# room_sensors.net
KiCad netlist of a schematic drawn in EAGLE
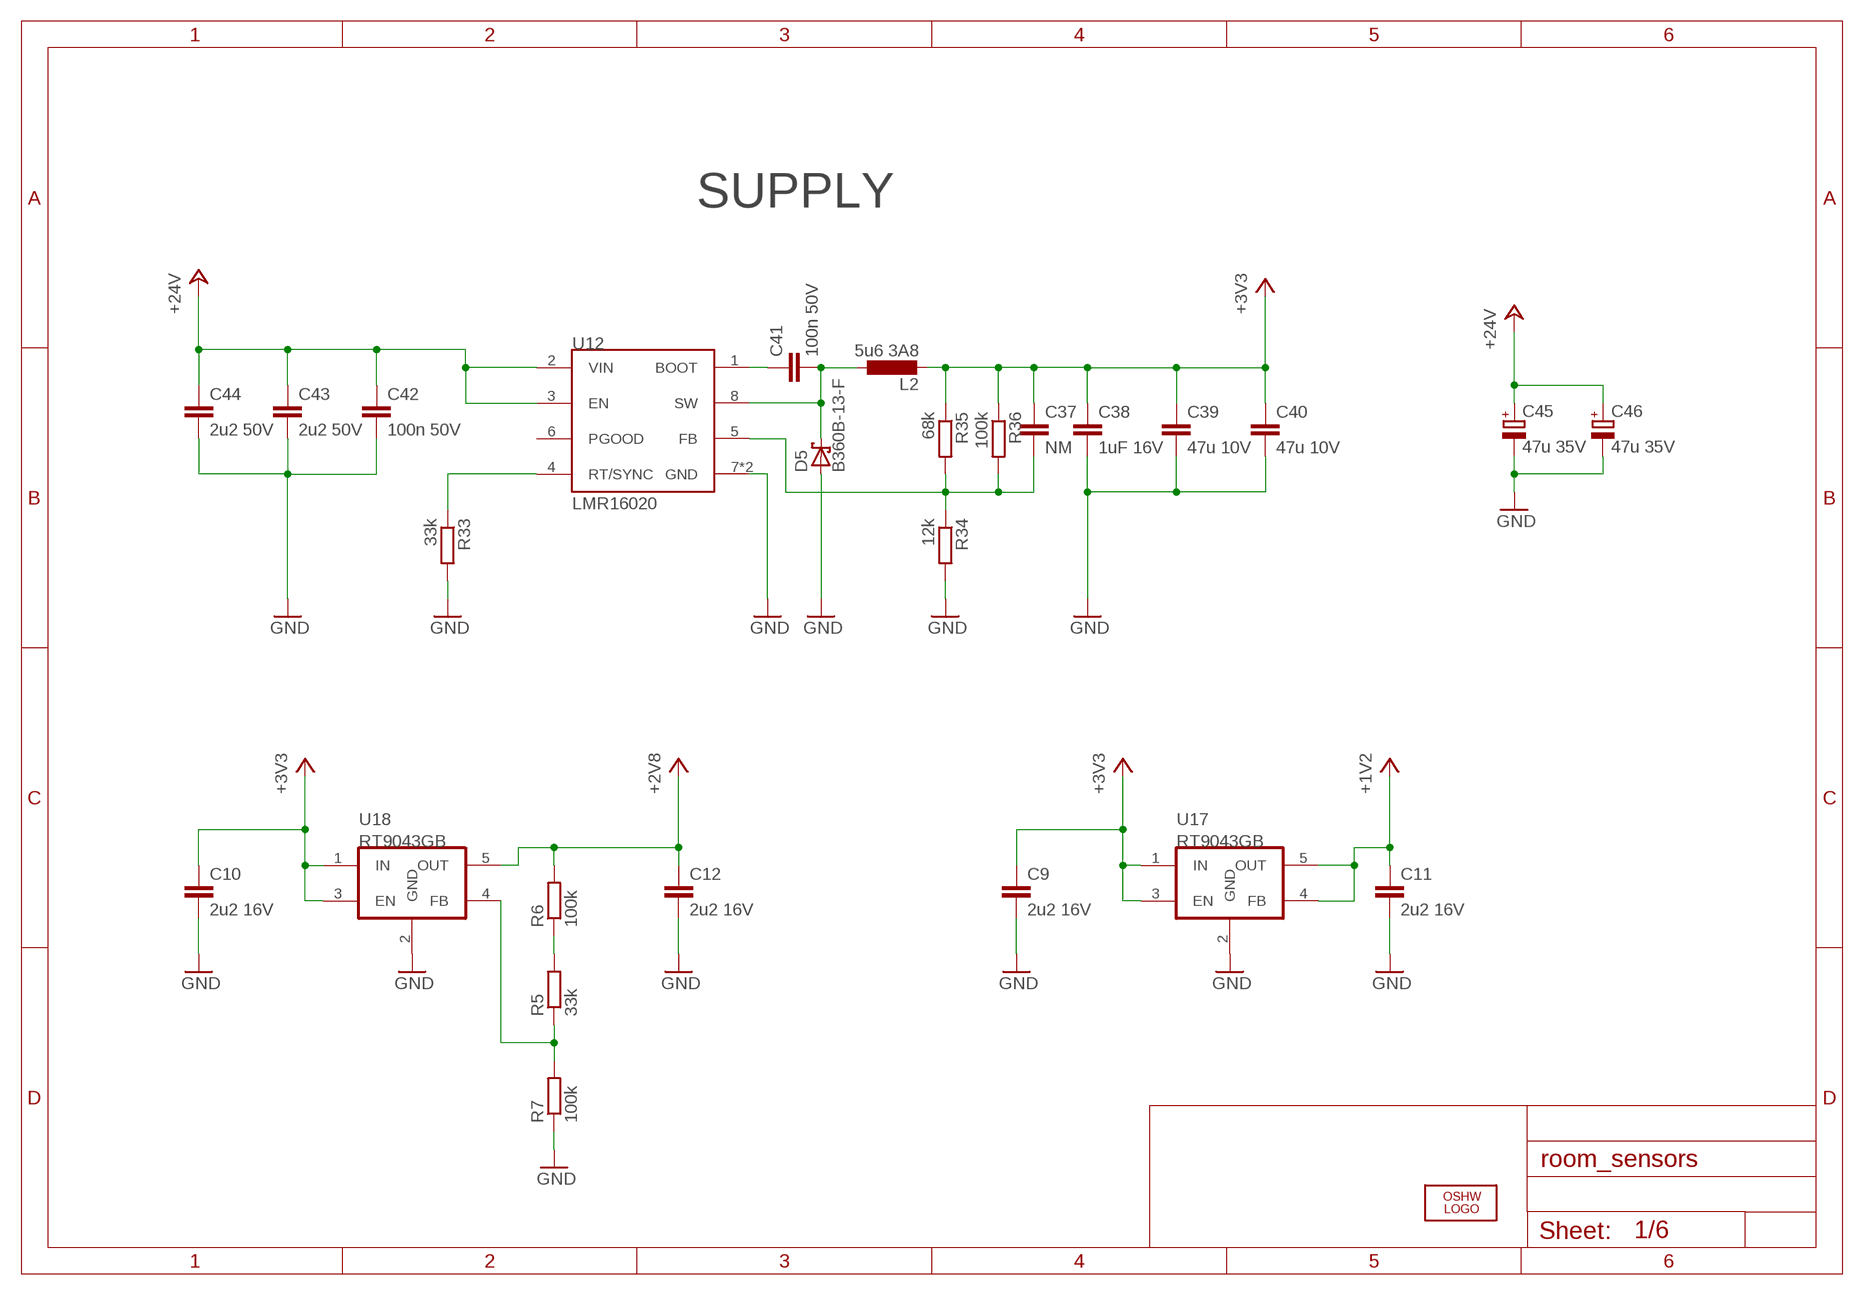
[diagram p0: schematic, sheet 1]
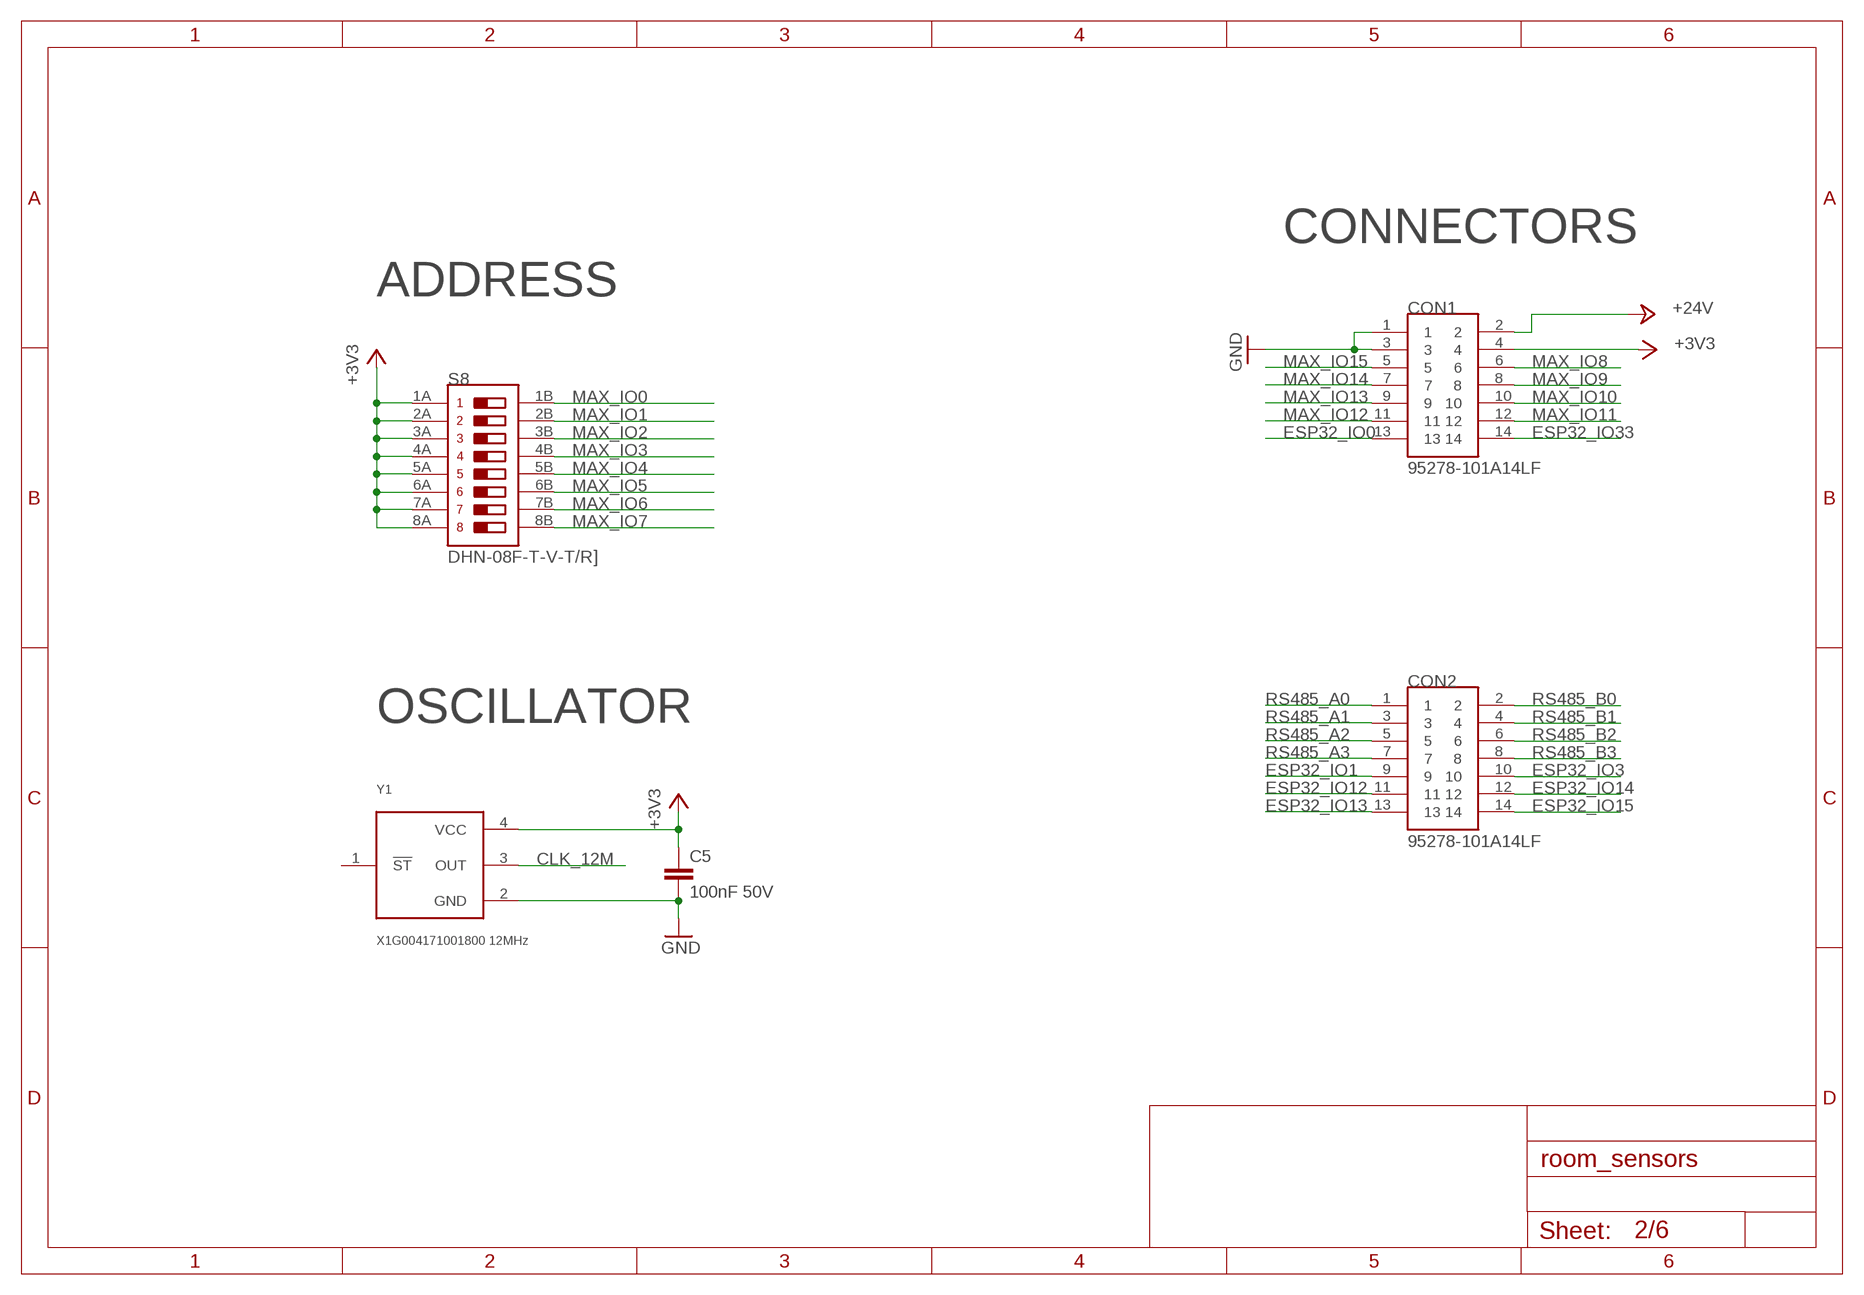
[diagram p1: schematic, sheet 2]
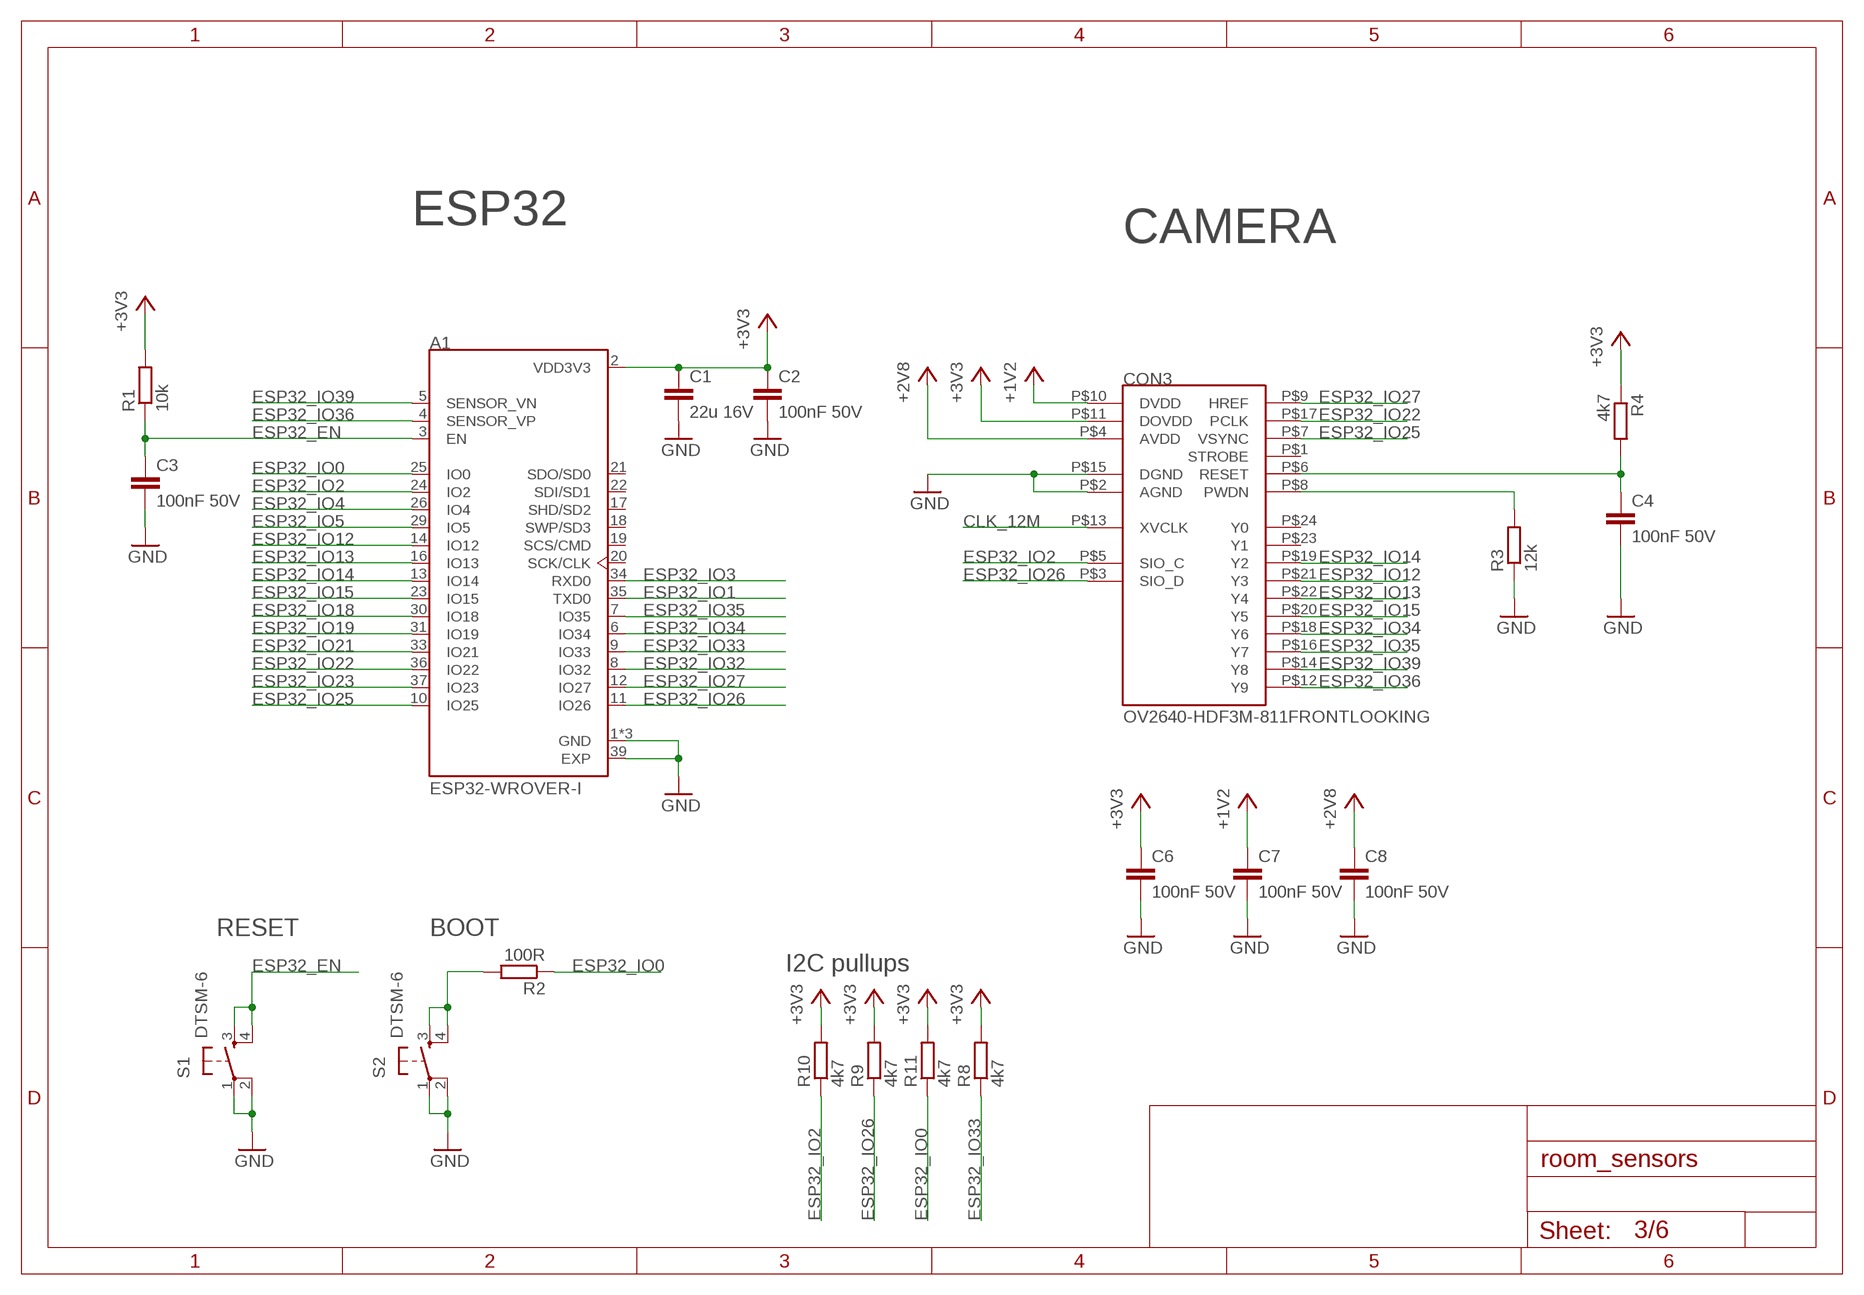
[diagram p2: schematic, sheet 3]
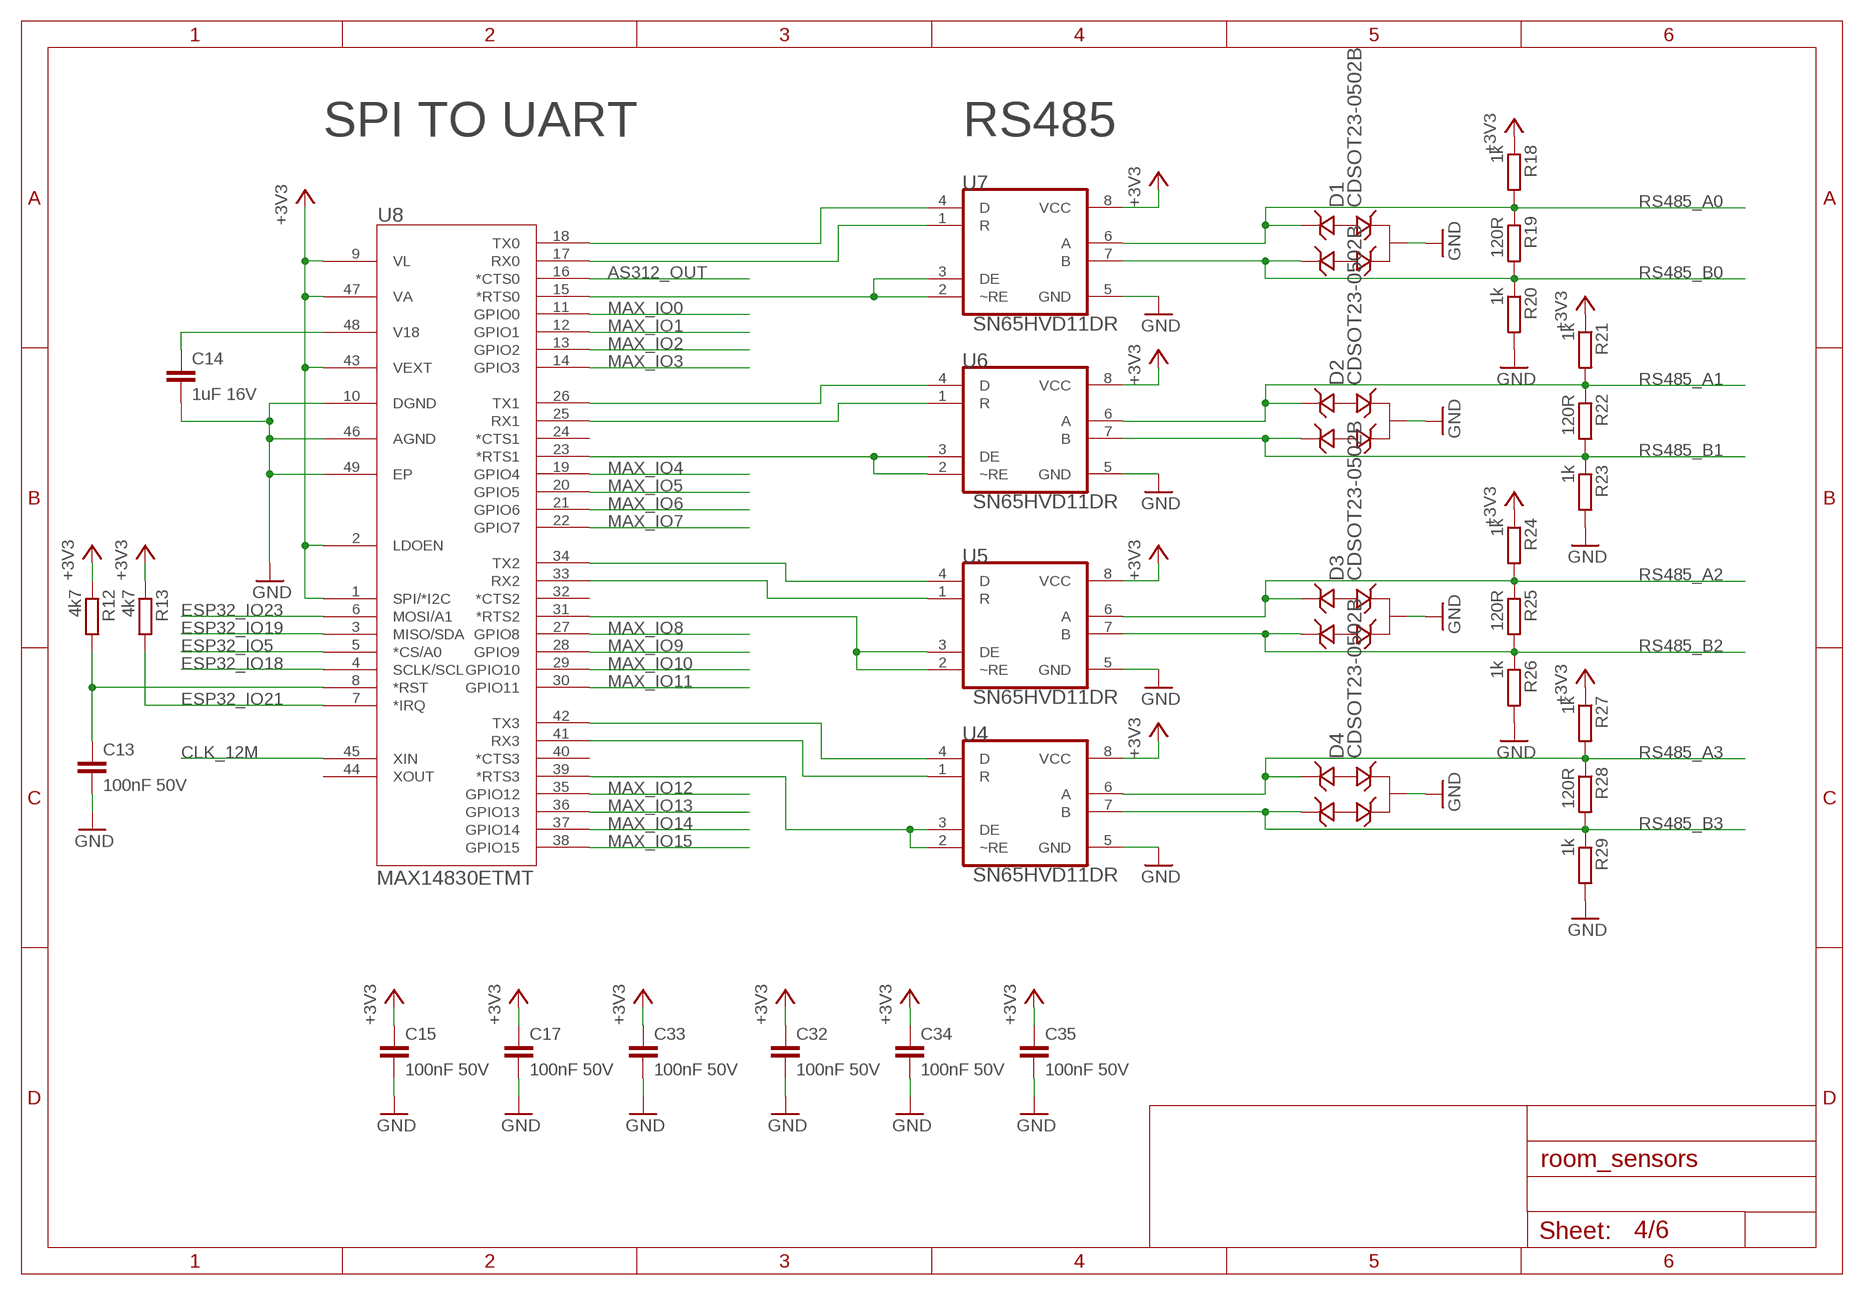
[diagram p3: schematic, sheet 4]
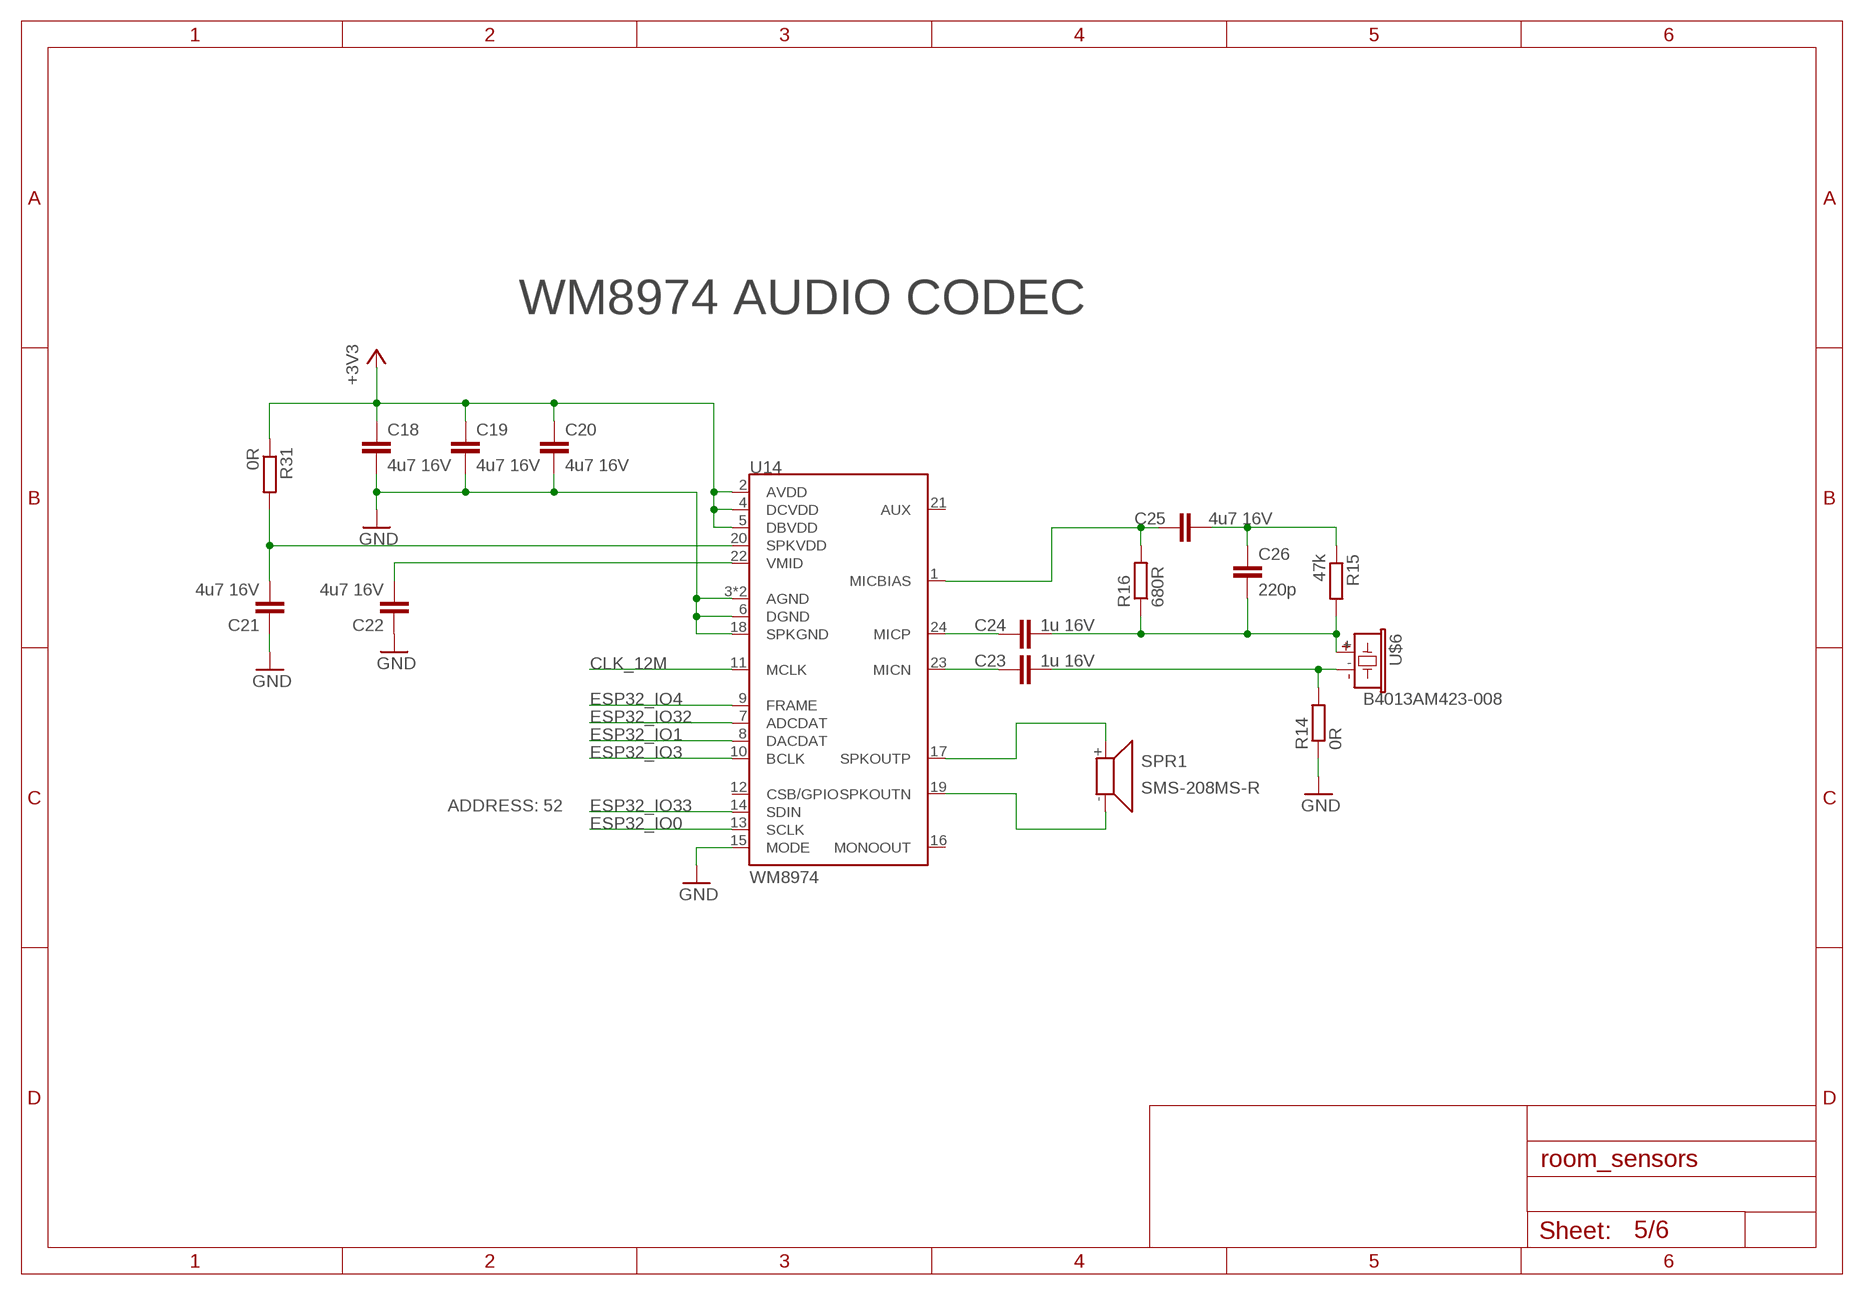
[diagram p4: schematic, sheet 5]
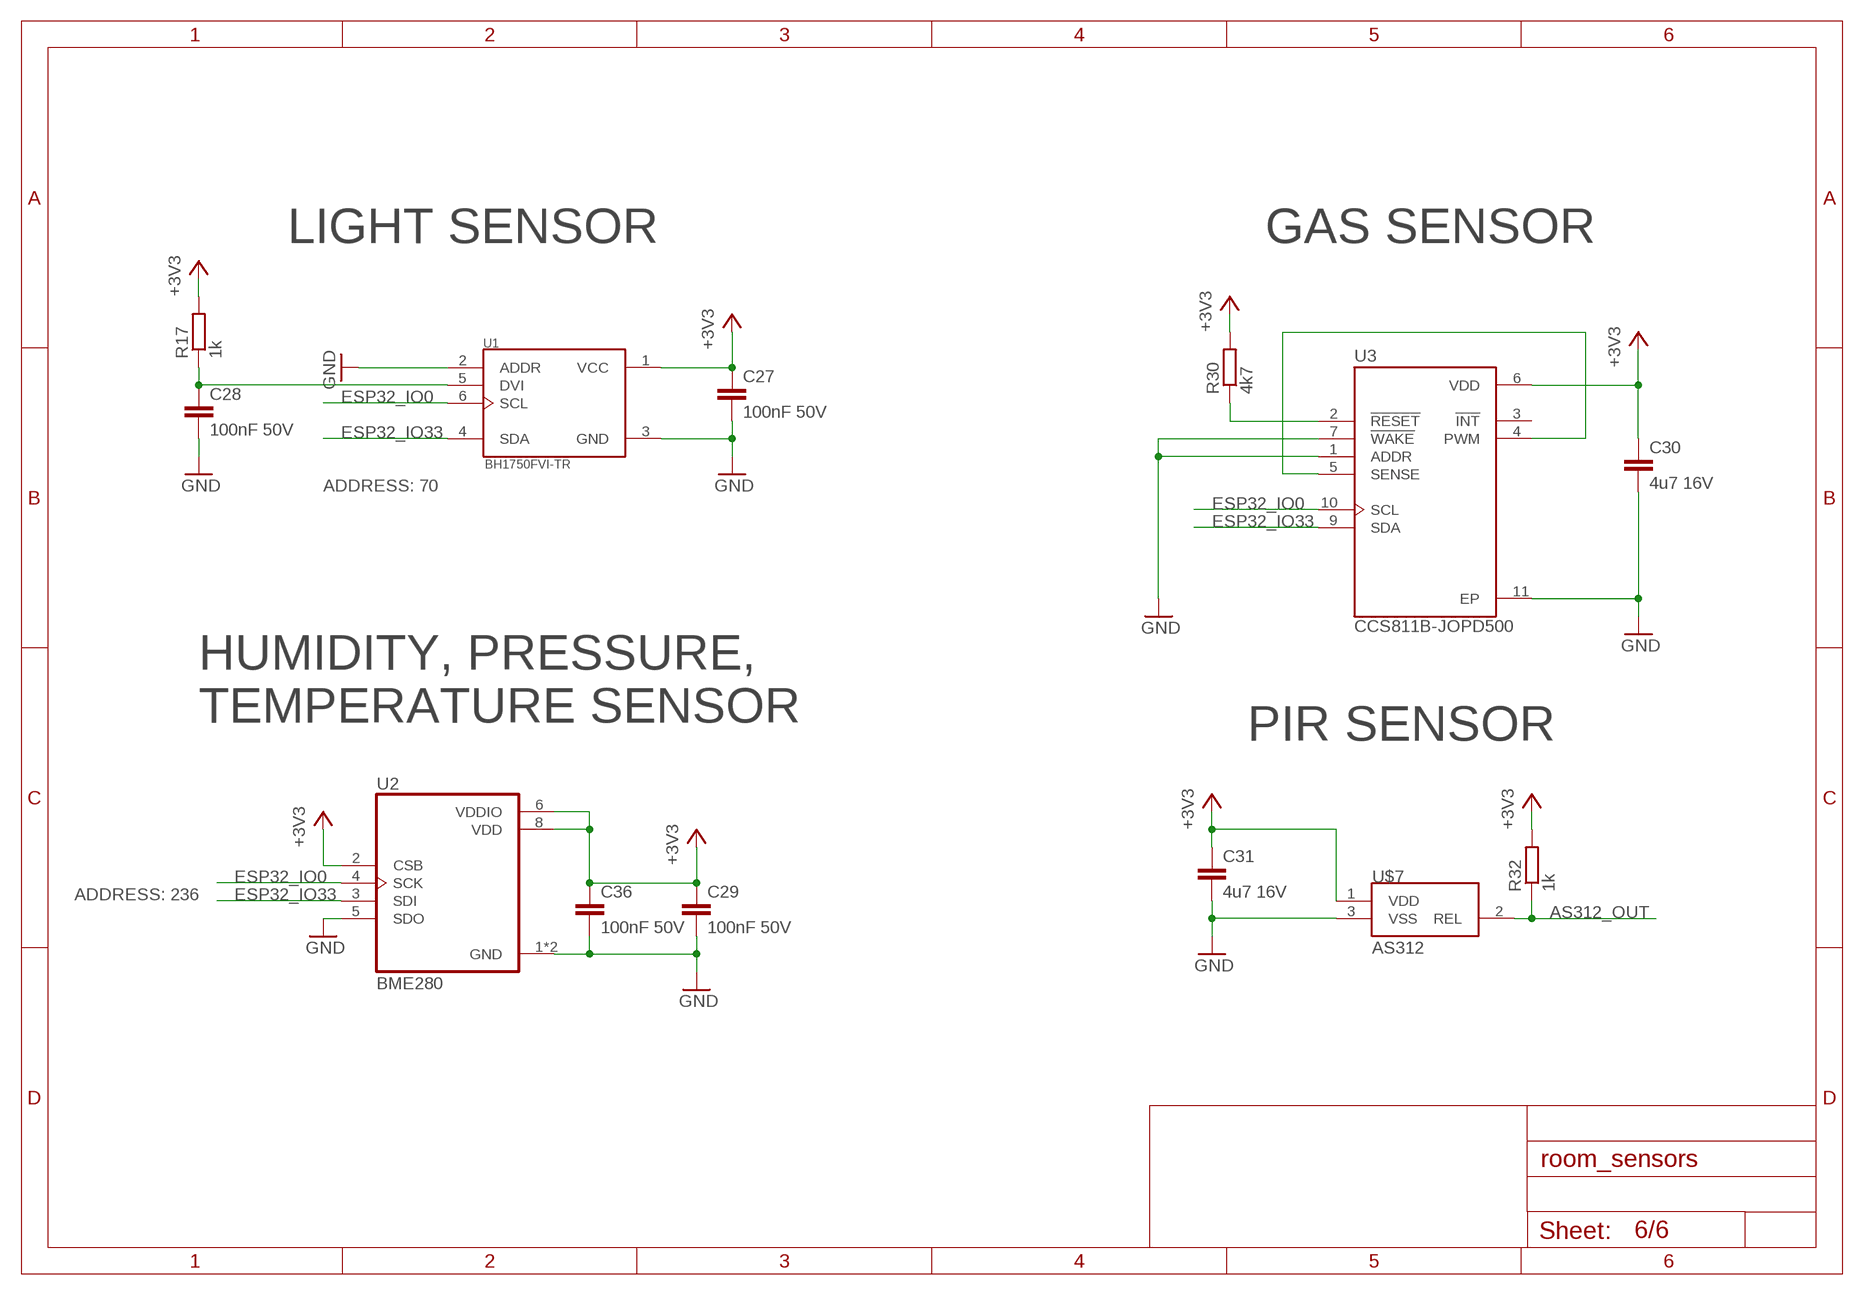
[diagram p5: schematic, sheet 6]

(export (version "E")
  (design (tool "Eeschema 10.0.6"))
  (components
    (comp (ref "C9")
      (value "2u2 16V")
      (footprint "eagle-import:C1206")
      (libsource (lib "eagle-import") (part "C-EUC1206"))
    )
    (comp (ref "C10")
      (value "2u2 16V")
      (footprint "eagle-import:C1206")
      (libsource (lib "eagle-import") (part "C-EUC1206"))
    )
    (comp (ref "C11")
      (value "2u2 16V")
      (footprint "eagle-import:C1206")
      (libsource (lib "eagle-import") (part "C-EUC1206"))
    )
    (comp (ref "C12")
      (value "2u2 16V")
      (footprint "eagle-import:C1206")
      (libsource (lib "eagle-import") (part "C-EUC1206"))
    )
    (comp (ref "C37")
      (value "NM")
      (footprint "eagle-import:C0805")
      (libsource (lib "eagle-import") (part "C-EUC0805"))
    )
    (comp (ref "C38")
      (value "1uF 16V")
      (footprint "eagle-import:C0805")
      (libsource (lib "eagle-import") (part "C-EUC0805"))
    )
    (comp (ref "C39")
      (value "47u 10V")
      (footprint "eagle-import:C1210")
      (libsource (lib "eagle-import") (part "C-EUC1210"))
    )
    (comp (ref "C40")
      (value "47u 10V")
      (footprint "eagle-import:C1210")
      (libsource (lib "eagle-import") (part "C-EUC1210"))
    )
    (comp (ref "C41")
      (value "100n 50V")
      (footprint "eagle-import:C1206")
      (libsource (lib "eagle-import") (part "C-EUC1206"))
    )
    (comp (ref "C42")
      (value "100n 50V")
      (footprint "eagle-import:C1206")
      (libsource (lib "eagle-import") (part "C-EUC1206"))
    )
    (comp (ref "C43")
      (value "2u2 50V")
      (footprint "eagle-import:C1206")
      (libsource (lib "eagle-import") (part "C-EUC1206"))
    )
    (comp (ref "C44")
      (value "2u2 50V")
      (footprint "eagle-import:C1206")
      (libsource (lib "eagle-import") (part "C-EUC1206"))
    )
    (comp (ref "C45")
      (value "47u 35V")
      (footprint "eagle-import:UD-5X5,8_NICHICON")
      (libsource (lib "eagle-import") (part "CPOL-EUUD-5X5,8"))
    )
    (comp (ref "C46")
      (value "47u 35V")
      (footprint "eagle-import:UD-5X5,8_NICHICON")
      (libsource (lib "eagle-import") (part "CPOL-EUUD-5X5,8"))
    )
    (comp (ref "D5")
      (value "B360B-13-F")
      (footprint "eagle-import:SMB")
      (libsource (lib "eagle-import") (part "MBRS130LT3"))
    )
    (comp (ref "L2")
      (value "5u6 3A8")
      (footprint "eagle-import:SLF10145T-150M2R2-PF")
      (libsource (lib "eagle-import") (part "SLF10145T-150M2R2-PF"))
    )
    (comp (ref "LOGO1")
      (value "OSHW_LOGO_FILLX0350-NT")
      (footprint "eagle-import:OSHW_FILLX350_NOTEXT")
      (libsource (lib "eagle-import") (part "OSHW_LOGO_FILLX0350-NT"))
    )
    (comp (ref "R5")
      (value "33k")
      (footprint "eagle-import:R1206")
      (libsource (lib "eagle-import") (part "R-EU_R1206"))
    )
    (comp (ref "R6")
      (value "100k")
      (footprint "eagle-import:R1206")
      (libsource (lib "eagle-import") (part "R-EU_R1206"))
    )
    (comp (ref "R7")
      (value "100k")
      (footprint "eagle-import:R1206")
      (libsource (lib "eagle-import") (part "R-EU_R1206"))
    )
    (comp (ref "R33")
      (value "33k")
      (footprint "eagle-import:R1206")
      (libsource (lib "eagle-import") (part "R-EU_R1206"))
    )
    (comp (ref "R34")
      (value "12k")
      (footprint "eagle-import:R1206")
      (libsource (lib "eagle-import") (part "R-EU_R1206"))
    )
    (comp (ref "R35")
      (value "68k")
      (footprint "eagle-import:R1206")
      (libsource (lib "eagle-import") (part "R-EU_R1206"))
    )
    (comp (ref "R36")
      (value "100k")
      (footprint "eagle-import:R1206")
      (libsource (lib "eagle-import") (part "R-EU_R1206"))
    )
    (comp (ref "U12")
      (value "LMR16020")
      (footprint "eagle-import:SOIC127P600X170-8N")
      (libsource (lib "eagle-import") (part "LMR16020"))
    )
    (comp (ref "U17")
      (value "RT9043GB")
      (footprint "eagle-import:SOP95P275X110-5N")
      (libsource (lib "eagle-import") (part "RT9043GB"))
    )
    (comp (ref "U18")
      (value "RT9043GB")
      (footprint "eagle-import:SOP95P275X110-5N")
      (libsource (lib "eagle-import") (part "RT9043GB"))
    )
    (comp (ref "C27")
      (value "100nF 50V")
      (footprint "eagle-import:C0805")
      (libsource (lib "eagle-import") (part "C-EUC0805"))
    )
    (comp (ref "C28")
      (value "100nF 50V")
      (footprint "eagle-import:C0805")
      (libsource (lib "eagle-import") (part "C-EUC0805"))
    )
    (comp (ref "C29")
      (value "100nF 50V")
      (footprint "eagle-import:C0805")
      (libsource (lib "eagle-import") (part "C-EUC0805"))
    )
    (comp (ref "C30")
      (value "4u7 16V")
      (footprint "eagle-import:C0805")
      (libsource (lib "eagle-import") (part "C-EUC0805"))
    )
    (comp (ref "C31")
      (value "4u7 16V")
      (footprint "eagle-import:C0805")
      (libsource (lib "eagle-import") (part "C-EUC0805"))
    )
    (comp (ref "C36")
      (value "100nF 50V")
      (footprint "eagle-import:C0805")
      (libsource (lib "eagle-import") (part "C-EUC0805"))
    )
    (comp (ref "R17")
      (value "1k")
      (footprint "eagle-import:R1206")
      (libsource (lib "eagle-import") (part "R-EU_R1206"))
    )
    (comp (ref "R30")
      (value "4k7")
      (footprint "eagle-import:R1206")
      (libsource (lib "eagle-import") (part "R-EU_R1206"))
    )
    (comp (ref "R32")
      (value "1k")
      (footprint "eagle-import:R1206")
      (libsource (lib "eagle-import") (part "R-EU_R1206"))
    )
    (comp (ref "U$7")
      (value "AS312")
      (footprint "eagle-import:TO-39")
      (libsource (lib "eagle-import") (part "AS312"))
    )
    (comp (ref "U1")
      (value "BH1750FVI-TR")
      (footprint "eagle-import:SOTFL50P300X75-6N")
      (fields (field (name "MF") "Rohm"))
      (libsource (lib "eagle-import") (part "BH1750FVI-TR"))
    )
    (comp (ref "U2")
      (value "BME280")
      (footprint "eagle-import:PSON65P250X250X100-8N")
      (fields (field (name "MF") "Bosch"))
      (libsource (lib "eagle-import") (part "BME280"))
    )
    (comp (ref "U3")
      (value "CCS811B-JOPD500")
      (footprint "eagle-import:SON60P400X270X110-11N")
      (fields (field (name "MF") "ams"))
      (libsource (lib "eagle-import") (part "CCS811B-JOPD500"))
    )
    (comp (ref "C13")
      (value "100nF 50V")
      (footprint "eagle-import:C0805")
      (libsource (lib "eagle-import") (part "C-EUC0805"))
    )
    (comp (ref "C14")
      (value "1uF 16V")
      (footprint "eagle-import:C0805")
      (libsource (lib "eagle-import") (part "C-EUC0805"))
    )
    (comp (ref "C15")
      (value "100nF 50V")
      (footprint "eagle-import:C0805")
      (libsource (lib "eagle-import") (part "C-EUC0805"))
    )
    (comp (ref "C17")
      (value "100nF 50V")
      (footprint "eagle-import:C0805")
      (libsource (lib "eagle-import") (part "C-EUC0805"))
    )
    (comp (ref "C32")
      (value "100nF 50V")
      (footprint "eagle-import:C0805")
      (libsource (lib "eagle-import") (part "C-EUC0805"))
    )
    (comp (ref "C33")
      (value "100nF 50V")
      (footprint "eagle-import:C0805")
      (libsource (lib "eagle-import") (part "C-EUC0805"))
    )
    (comp (ref "C34")
      (value "100nF 50V")
      (footprint "eagle-import:C0805")
      (libsource (lib "eagle-import") (part "C-EUC0805"))
    )
    (comp (ref "C35")
      (value "100nF 50V")
      (footprint "eagle-import:C0805")
      (libsource (lib "eagle-import") (part "C-EUC0805"))
    )
    (comp (ref "D1")
      (value "CDSOT23-0502B")
      (footprint "eagle-import:SOT-23-3")
      (fields (field (name "MF") "Bourns") (field (name "MP") "CDSOT23-SM712"))
      (libsource (lib "eagle-import") (part "CDSOT23-SM712"))
    )
    (comp (ref "D2")
      (value "CDSOT23-0502B")
      (footprint "eagle-import:SOT-23-3")
      (fields (field (name "MF") "Bourns") (field (name "MP") "CDSOT23-SM712"))
      (libsource (lib "eagle-import") (part "CDSOT23-SM712"))
    )
    (comp (ref "D3")
      (value "CDSOT23-0502B")
      (footprint "eagle-import:SOT-23-3")
      (fields (field (name "MF") "Bourns") (field (name "MP") "CDSOT23-SM712"))
      (libsource (lib "eagle-import") (part "CDSOT23-SM712"))
    )
    (comp (ref "D4")
      (value "CDSOT23-0502B")
      (footprint "eagle-import:SOT-23-3")
      (fields (field (name "MF") "Bourns") (field (name "MP") "CDSOT23-SM712"))
      (libsource (lib "eagle-import") (part "CDSOT23-SM712"))
    )
    (comp (ref "R12")
      (value "4k7")
      (footprint "eagle-import:R1206")
      (libsource (lib "eagle-import") (part "R-EU_R1206"))
    )
    (comp (ref "R13")
      (value "4k7")
      (footprint "eagle-import:R1206")
      (libsource (lib "eagle-import") (part "R-EU_R1206"))
    )
    (comp (ref "R18")
      (value "1k")
      (footprint "eagle-import:R1206")
      (libsource (lib "eagle-import") (part "R-EU_R1206"))
    )
    (comp (ref "R19")
      (value "120R")
      (footprint "eagle-import:R1206")
      (libsource (lib "eagle-import") (part "R-EU_R1206"))
    )
    (comp (ref "R20")
      (value "1k")
      (footprint "eagle-import:R1206")
      (libsource (lib "eagle-import") (part "R-EU_R1206"))
    )
    (comp (ref "R21")
      (value "1k")
      (footprint "eagle-import:R1206")
      (libsource (lib "eagle-import") (part "R-EU_R1206"))
    )
    (comp (ref "R22")
      (value "120R")
      (footprint "eagle-import:R1206")
      (libsource (lib "eagle-import") (part "R-EU_R1206"))
    )
    (comp (ref "R23")
      (value "1k")
      (footprint "eagle-import:R1206")
      (libsource (lib "eagle-import") (part "R-EU_R1206"))
    )
    (comp (ref "R24")
      (value "1k")
      (footprint "eagle-import:R1206")
      (libsource (lib "eagle-import") (part "R-EU_R1206"))
    )
    (comp (ref "R25")
      (value "120R")
      (footprint "eagle-import:R1206")
      (libsource (lib "eagle-import") (part "R-EU_R1206"))
    )
    (comp (ref "R26")
      (value "1k")
      (footprint "eagle-import:R1206")
      (libsource (lib "eagle-import") (part "R-EU_R1206"))
    )
    (comp (ref "R27")
      (value "1k")
      (footprint "eagle-import:R1206")
      (libsource (lib "eagle-import") (part "R-EU_R1206"))
    )
    (comp (ref "R28")
      (value "120R")
      (footprint "eagle-import:R1206")
      (libsource (lib "eagle-import") (part "R-EU_R1206"))
    )
    (comp (ref "R29")
      (value "1k")
      (footprint "eagle-import:R1206")
      (libsource (lib "eagle-import") (part "R-EU_R1206"))
    )
    (comp (ref "U4")
      (value "SN65HVD11DR")
      (footprint "eagle-import:SOIC127P600X175-8N")
      (fields (field (name "MF") "Texas Instruments"))
      (libsource (lib "eagle-import") (part "SN65HVD11DR"))
    )
    (comp (ref "U5")
      (value "SN65HVD11DR")
      (footprint "eagle-import:SOIC127P600X175-8N")
      (fields (field (name "MF") "Texas Instruments"))
      (libsource (lib "eagle-import") (part "SN65HVD11DR"))
    )
    (comp (ref "U6")
      (value "SN65HVD11DR")
      (footprint "eagle-import:SOIC127P600X175-8N")
      (fields (field (name "MF") "Texas Instruments"))
      (libsource (lib "eagle-import") (part "SN65HVD11DR"))
    )
    (comp (ref "U7")
      (value "SN65HVD11DR")
      (footprint "eagle-import:SOIC127P600X175-8N")
      (fields (field (name "MF") "Texas Instruments"))
      (libsource (lib "eagle-import") (part "SN65HVD11DR"))
    )
    (comp (ref "U8")
      (value "MAX14830ETMT")
      (footprint "eagle-import:21-0144H_T4877-3")
      (fields (field (name "MF") "Maxim Integrated") (field (name "MP") "MAX14830ETM+"))
      (libsource (lib "eagle-import") (part "MAX14830ETMT"))
    )
    (comp (ref "A1")
      (value "ESP32-WROVER-I")
      (footprint "eagle-import:XCVR_ESP32-WROVER-I")
      (fields (field (name "MF") "Espressif Systems"))
      (libsource (lib "eagle-import") (part "ESP32-WROVER-I"))
    )
    (comp (ref "C1")
      (value "22u 16V")
      (footprint "eagle-import:C1210")
      (libsource (lib "eagle-import") (part "C-EUC1210"))
    )
    (comp (ref "C2")
      (value "100nF 50V")
      (footprint "eagle-import:C0805")
      (libsource (lib "eagle-import") (part "C-EUC0805"))
    )
    (comp (ref "C3")
      (value "100nF 50V")
      (footprint "eagle-import:C0805")
      (libsource (lib "eagle-import") (part "C-EUC0805"))
    )
    (comp (ref "C4")
      (value "100nF 50V")
      (footprint "eagle-import:C0805")
      (libsource (lib "eagle-import") (part "C-EUC0805"))
    )
    (comp (ref "C6")
      (value "100nF 50V")
      (footprint "eagle-import:C0805")
      (libsource (lib "eagle-import") (part "C-EUC0805"))
    )
    (comp (ref "C7")
      (value "100nF 50V")
      (footprint "eagle-import:C0805")
      (libsource (lib "eagle-import") (part "C-EUC0805"))
    )
    (comp (ref "C8")
      (value "100nF 50V")
      (footprint "eagle-import:C0805")
      (libsource (lib "eagle-import") (part "C-EUC0805"))
    )
    (comp (ref "CON3")
      (value "OV2640-HDF3M-811FRONTLOOKING")
      (footprint "eagle-import:FH34SRJ-24S-0.5SH(50)")
      (libsource (lib "eagle-import") (part "OV2640-HDF3M-811FRONTLOOKING"))
    )
    (comp (ref "R1")
      (value "10k")
      (footprint "eagle-import:R1206")
      (libsource (lib "eagle-import") (part "R-EU_R1206"))
    )
    (comp (ref "R2")
      (value "100R")
      (footprint "eagle-import:R1206")
      (libsource (lib "eagle-import") (part "R-EU_R1206"))
    )
    (comp (ref "R3")
      (value "12k")
      (footprint "eagle-import:R1206")
      (libsource (lib "eagle-import") (part "R-EU_R1206"))
    )
    (comp (ref "R4")
      (value "4k7")
      (footprint "eagle-import:R1206")
      (libsource (lib "eagle-import") (part "R-EU_R1206"))
    )
    (comp (ref "R8")
      (value "4k7")
      (footprint "eagle-import:R1206")
      (libsource (lib "eagle-import") (part "R-EU_R1206"))
    )
    (comp (ref "R9")
      (value "4k7")
      (footprint "eagle-import:R1206")
      (libsource (lib "eagle-import") (part "R-EU_R1206"))
    )
    (comp (ref "R10")
      (value "4k7")
      (footprint "eagle-import:R1206")
      (libsource (lib "eagle-import") (part "R-EU_R1206"))
    )
    (comp (ref "R11")
      (value "4k7")
      (footprint "eagle-import:R1206")
      (libsource (lib "eagle-import") (part "R-EU_R1206"))
    )
    (comp (ref "S1")
      (value "DTSM-6")
      (footprint "eagle-import:DTSM-6")
      (libsource (lib "eagle-import") (part "DTSM-6"))
    )
    (comp (ref "S2")
      (value "DTSM-6")
      (footprint "eagle-import:DTSM-6")
      (libsource (lib "eagle-import") (part "DTSM-6"))
    )
    (comp (ref "C18")
      (value "4u7 16V")
      (footprint "eagle-import:C0805")
      (libsource (lib "eagle-import") (part "C-EUC0805"))
    )
    (comp (ref "C19")
      (value "4u7 16V")
      (footprint "eagle-import:C0805")
      (libsource (lib "eagle-import") (part "C-EUC0805"))
    )
    (comp (ref "C20")
      (value "4u7 16V")
      (footprint "eagle-import:C0805")
      (libsource (lib "eagle-import") (part "C-EUC0805"))
    )
    (comp (ref "C21")
      (value "4u7 16V")
      (footprint "eagle-import:C0805")
      (libsource (lib "eagle-import") (part "C-EUC0805"))
    )
    (comp (ref "C22")
      (value "4u7 16V")
      (footprint "eagle-import:C0805")
      (libsource (lib "eagle-import") (part "C-EUC0805"))
    )
    (comp (ref "C23")
      (value "1u 16V")
      (footprint "eagle-import:C0805")
      (libsource (lib "eagle-import") (part "C-EUC0805"))
    )
    (comp (ref "C24")
      (value "1u 16V")
      (footprint "eagle-import:C0805")
      (libsource (lib "eagle-import") (part "C-EUC0805"))
    )
    (comp (ref "C25")
      (value "4u7 16V")
      (footprint "eagle-import:C0805")
      (libsource (lib "eagle-import") (part "C-EUC0805"))
    )
    (comp (ref "C26")
      (value "220p")
      (footprint "eagle-import:C0805")
      (libsource (lib "eagle-import") (part "C-EUC0805"))
    )
    (comp (ref "R14")
      (value "0R")
      (footprint "eagle-import:R1206")
      (libsource (lib "eagle-import") (part "R-EU_R1206"))
    )
    (comp (ref "R15")
      (value "47k")
      (footprint "eagle-import:R1206")
      (libsource (lib "eagle-import") (part "R-EU_R1206"))
    )
    (comp (ref "R16")
      (value "680R")
      (footprint "eagle-import:R1206")
      (libsource (lib "eagle-import") (part "R-EU_R1206"))
    )
    (comp (ref "R31")
      (value "0R")
      (footprint "eagle-import:R0603")
      (libsource (lib "eagle-import") (part "R-EU_R0603"))
    )
    (comp (ref "SPR1")
      (value "SMS-208MS-R")
      (footprint "eagle-import:SMS-2008MS-R")
      (libsource (lib "eagle-import") (part "SMS-208MS-R"))
    )
    (comp (ref "U$6")
      (value "B4013AM423-008")
      (footprint "eagle-import:MIC")
      (libsource (lib "eagle-import") (part "B4013AM423-008"))
    )
    (comp (ref "U14")
      (value "WM8974")
      (footprint "eagle-import:QFN-24_ALT2")
      (libsource (lib "eagle-import") (part "WM8974"))
    )
    (comp (ref "C5")
      (value "100nF 50V")
      (footprint "eagle-import:C0805")
      (libsource (lib "eagle-import") (part "C-EUC0805"))
    )
    (comp (ref "CON1")
      (value "95278-101A14LF")
      (footprint "eagle-import:95278-101A14LF")
      (libsource (lib "eagle-import") (part "95278-101A14LF"))
    )
    (comp (ref "CON2")
      (value "95278-101A14LF")
      (footprint "eagle-import:95278-101A14LF")
      (libsource (lib "eagle-import") (part "95278-101A14LF"))
    )
    (comp (ref "S8")
      (value "DHN-08F-T-V-T/R]")
      (footprint "eagle-import:DHN-08F-T-V-T_R]")
      (libsource (lib "eagle-import") (part "DHN-08F-T-V-T/R]"))
    )
    (comp (ref "Y1")
      (value "X1G004171001800 12MHz")
      (footprint "eagle-import:OSCCC250X200X80-4N")
      (fields (field (name "MF") "EPSON") (field (name "MP") "X1G0041710033"))
      (libsource (lib "eagle-import") (part "X1G0041710033"))
    )
  )
  (nets
    (net (code "1") (name "+1V2") (class "Default")
      (node (ref "C11") (pin "1") (pinfunction "1_1") (pintype "passive"))
      (node (ref "C7") (pin "1") (pinfunction "1_1") (pintype "passive"))
      (node (ref "CON3") (pin "P$10") (pinfunction "DVDD_P$10") (pintype "power_in"))
      (node (ref "U17") (pin "4") (pinfunction "FB_4") (pintype "power_in"))
      (node (ref "U17") (pin "5") (pinfunction "OUT_5") (pintype "power_in"))
    )
    (net (code "2") (name "+2V8") (class "Default")
      (node (ref "C12") (pin "1") (pinfunction "1_1") (pintype "passive"))
      (node (ref "C8") (pin "1") (pinfunction "1_1") (pintype "passive"))
      (node (ref "CON3") (pin "P$4") (pinfunction "AVDD_P$4") (pintype "power_in"))
      (node (ref "R6") (pin "2") (pinfunction "2_2") (pintype "passive"))
      (node (ref "U18") (pin "5") (pinfunction "OUT_5") (pintype "power_in"))
    )
    (net (code "3") (name "+3V3") (class "Default")
      (node (ref "A1") (pin "2") (pinfunction "VDD3V3_2") (pintype "power_in"))
      (node (ref "C1") (pin "1") (pinfunction "1_1") (pintype "passive"))
      (node (ref "C10") (pin "1") (pinfunction "1_1") (pintype "passive"))
      (node (ref "C15") (pin "1") (pinfunction "1_1") (pintype "passive"))
      (node (ref "C17") (pin "1") (pinfunction "1_1") (pintype "passive"))
      (node (ref "C18") (pin "1") (pinfunction "1_1") (pintype "passive"))
      (node (ref "C19") (pin "1") (pinfunction "1_1") (pintype "passive"))
      (node (ref "C2") (pin "1") (pinfunction "1_1") (pintype "passive"))
      (node (ref "C20") (pin "1") (pinfunction "1_1") (pintype "passive"))
      (node (ref "C27") (pin "1") (pinfunction "1_1") (pintype "passive"))
      (node (ref "C29") (pin "1") (pinfunction "1_1") (pintype "passive"))
      (node (ref "C30") (pin "1") (pinfunction "1_1") (pintype "passive"))
      (node (ref "C31") (pin "1") (pinfunction "1_1") (pintype "passive"))
      (node (ref "C32") (pin "1") (pinfunction "1_1") (pintype "passive"))
      (node (ref "C33") (pin "1") (pinfunction "1_1") (pintype "passive"))
      (node (ref "C34") (pin "1") (pinfunction "1_1") (pintype "passive"))
      (node (ref "C35") (pin "1") (pinfunction "1_1") (pintype "passive"))
      (node (ref "C36") (pin "1") (pinfunction "1_1") (pintype "passive"))
      (node (ref "C37") (pin "1") (pinfunction "1_1") (pintype "passive"))
      (node (ref "C38") (pin "1") (pinfunction "1_1") (pintype "passive"))
      (node (ref "C39") (pin "1") (pinfunction "1_1") (pintype "passive"))
      (node (ref "C40") (pin "1") (pinfunction "1_1") (pintype "passive"))
      (node (ref "C5") (pin "1") (pinfunction "1_1") (pintype "passive"))
      (node (ref "C6") (pin "1") (pinfunction "1_1") (pintype "passive"))
      (node (ref "C9") (pin "1") (pinfunction "1_1") (pintype "passive"))
      (node (ref "CON1") (pin "4") (pinfunction "4_4") (pintype "passive"))
      (node (ref "CON3") (pin "P$11") (pinfunction "DOVDD_P$11") (pintype "power_in"))
      (node (ref "L2") (pin "P$2") (pinfunction "2_P$2") (pintype "passive"))
      (node (ref "R1") (pin "2") (pinfunction "2_2") (pintype "passive"))
      (node (ref "R10") (pin "2") (pinfunction "2_2") (pintype "passive"))
      (node (ref "R11") (pin "2") (pinfunction "2_2") (pintype "passive"))
      (node (ref "R12") (pin "1") (pinfunction "1_1") (pintype "passive"))
      (node (ref "R13") (pin "1") (pinfunction "1_1") (pintype "passive"))
      (node (ref "R17") (pin "2") (pinfunction "2_2") (pintype "passive"))
      (node (ref "R18") (pin "1") (pinfunction "1_1") (pintype "passive"))
      (node (ref "R21") (pin "1") (pinfunction "1_1") (pintype "passive"))
      (node (ref "R24") (pin "1") (pinfunction "1_1") (pintype "passive"))
      (node (ref "R27") (pin "1") (pinfunction "1_1") (pintype "passive"))
      (node (ref "R30") (pin "2") (pinfunction "2_2") (pintype "passive"))
      (node (ref "R31") (pin "1") (pinfunction "1_1") (pintype "passive"))
      (node (ref "R32") (pin "2") (pinfunction "2_2") (pintype "passive"))
      (node (ref "R35") (pin "1") (pinfunction "1_1") (pintype "passive"))
      (node (ref "R36") (pin "1") (pinfunction "1_1") (pintype "passive"))
      (node (ref "R4") (pin "1") (pinfunction "1_1") (pintype "passive"))
      (node (ref "R8") (pin "2") (pinfunction "2_2") (pintype "passive"))
      (node (ref "R9") (pin "2") (pinfunction "2_2") (pintype "passive"))
      (node (ref "S8") (pin "1A") (pinfunction "1A_1A") (pintype "passive"))
      (node (ref "S8") (pin "2A") (pinfunction "2A_2A") (pintype "passive"))
      (node (ref "S8") (pin "3A") (pinfunction "3A_3A") (pintype "passive"))
      (node (ref "S8") (pin "4A") (pinfunction "4A_4A") (pintype "passive"))
      (node (ref "S8") (pin "5A") (pinfunction "5A_5A") (pintype "passive"))
      (node (ref "S8") (pin "6A") (pinfunction "6A_6A") (pintype "passive"))
      (node (ref "S8") (pin "7A") (pinfunction "7A_7A") (pintype "passive"))
      (node (ref "S8") (pin "8A") (pinfunction "8A_8A") (pintype "passive"))
      (node (ref "U$7") (pin "1") (pinfunction "VDD_1") (pintype "power_in"))
      (node (ref "U1") (pin "1") (pinfunction "VCC_1") (pintype "power_in"))
      (node (ref "U14") (pin "2") (pinfunction "AVDD_2") (pintype "power_in"))
      (node (ref "U14") (pin "4") (pinfunction "DCVDD_4") (pintype "power_in"))
      (node (ref "U14") (pin "5") (pinfunction "DBVDD_5") (pintype "power_in"))
      (node (ref "U17") (pin "1") (pinfunction "IN_1") (pintype "power_in"))
      (node (ref "U17") (pin "3") (pinfunction "EN_3") (pintype "power_in"))
      (node (ref "U18") (pin "1") (pinfunction "IN_1") (pintype "power_in"))
      (node (ref "U18") (pin "3") (pinfunction "EN_3") (pintype "power_in"))
      (node (ref "U2") (pin "2") (pinfunction "CSB_2") (pintype "input"))
      (node (ref "U2") (pin "6") (pinfunction "VDDIO_6") (pintype "power_in"))
      (node (ref "U2") (pin "8") (pinfunction "VDD_8") (pintype "power_in"))
      (node (ref "U3") (pin "6") (pinfunction "VDD_6") (pintype "power_in"))
      (node (ref "U4") (pin "8") (pinfunction "VCC_8") (pintype "power_in"))
      (node (ref "U5") (pin "8") (pinfunction "VCC_8") (pintype "power_in"))
      (node (ref "U6") (pin "8") (pinfunction "VCC_8") (pintype "power_in"))
      (node (ref "U7") (pin "8") (pinfunction "VCC_8") (pintype "power_in"))
      (node (ref "U8") (pin "1") (pinfunction "SPI/*I2C_1") (pintype "passive"))
      (node (ref "U8") (pin "2") (pinfunction "LDOEN_2") (pintype "passive"))
      (node (ref "U8") (pin "43") (pinfunction "VEXT_43") (pintype "passive"))
      (node (ref "U8") (pin "47") (pinfunction "VA_47") (pintype "passive"))
      (node (ref "U8") (pin "9") (pinfunction "VL_9") (pintype "power_in"))
      (node (ref "Y1") (pin "4") (pinfunction "VCC_4") (pintype "power_in"))
    )
    (net (code "4") (name "+24V") (class "Default")
      (node (ref "C42") (pin "1") (pinfunction "1_1") (pintype "passive"))
      (node (ref "C43") (pin "1") (pinfunction "1_1") (pintype "passive"))
      (node (ref "C44") (pin "1") (pinfunction "1_1") (pintype "passive"))
      (node (ref "C45") (pin "+") (pinfunction "+_+") (pintype "passive"))
      (node (ref "C46") (pin "+") (pinfunction "+_+") (pintype "passive"))
      (node (ref "CON1") (pin "2") (pinfunction "2_2") (pintype "passive"))
      (node (ref "U12") (pin "2") (pinfunction "VIN_2") (pintype "power_in"))
      (node (ref "U12") (pin "3") (pinfunction "EN_3") (pintype "input"))
    )
    (net (code "5") (name "AS312_OUT") (class "Default")
      (node (ref "R32") (pin "1") (pinfunction "1_1") (pintype "passive"))
      (node (ref "U$7") (pin "2") (pinfunction "REL_2") (pintype "output"))
      (node (ref "U8") (pin "16") (pinfunction "*CTS0_16") (pintype "passive"))
    )
    (net (code "6") (name "CLK_12M") (class "Default")
      (node (ref "CON3") (pin "P$13") (pinfunction "XVCLK_P$13") (pintype "input"))
      (node (ref "U14") (pin "11") (pinfunction "MCLK_11") (pintype "input"))
      (node (ref "U8") (pin "45") (pinfunction "XIN_45") (pintype "passive"))
      (node (ref "Y1") (pin "3") (pinfunction "OUT_3") (pintype "output"))
    )
    (net (code "7") (name "ESP32_EN") (class "Default")
      (node (ref "A1") (pin "3") (pinfunction "EN_3") (pintype "input"))
      (node (ref "C3") (pin "1") (pinfunction "1_1") (pintype "passive"))
      (node (ref "R1") (pin "1") (pinfunction "1_1") (pintype "passive"))
      (node (ref "S1") (pin "3") (pinfunction "3_3") (pintype "passive"))
      (node (ref "S1") (pin "4") (pinfunction "4_4") (pintype "passive"))
    )
    (net (code "8") (name "ESP32_IO0") (class "Default")
      (node (ref "A1") (pin "25") (pinfunction "IO0_25") (pintype "bidirectional"))
      (node (ref "CON1") (pin "13") (pinfunction "13_13") (pintype "passive"))
      (node (ref "R11") (pin "1") (pinfunction "1_1") (pintype "passive"))
      (node (ref "R2") (pin "1") (pinfunction "1_1") (pintype "passive"))
      (node (ref "U1") (pin "6") (pinfunction "SCL_6") (pintype "input"))
      (node (ref "U14") (pin "13") (pinfunction "SCLK_13") (pintype "input"))
      (node (ref "U2") (pin "4") (pinfunction "SCK_4") (pintype "input"))
      (node (ref "U3") (pin "10") (pinfunction "SCL_10") (pintype "input"))
    )
    (net (code "9") (name "ESP32_IO1") (class "Default")
      (node (ref "A1") (pin "35") (pinfunction "TXD0_35") (pintype "bidirectional"))
      (node (ref "CON2") (pin "9") (pinfunction "9_9") (pintype "passive"))
      (node (ref "U14") (pin "8") (pinfunction "DACDAT_8") (pintype "input"))
    )
    (net (code "10") (name "ESP32_IO2") (class "Default")
      (node (ref "A1") (pin "24") (pinfunction "IO2_24") (pintype "bidirectional"))
      (node (ref "CON3") (pin "P$5") (pinfunction "SIO_C_P$5") (pintype "input"))
      (node (ref "R10") (pin "1") (pinfunction "1_1") (pintype "passive"))
    )
    (net (code "11") (name "ESP32_IO3") (class "Default")
      (node (ref "A1") (pin "34") (pinfunction "RXD0_34") (pintype "bidirectional"))
      (node (ref "CON2") (pin "10") (pinfunction "10_10") (pintype "passive"))
      (node (ref "U14") (pin "10") (pinfunction "BCLK_10") (pintype "bidirectional"))
    )
    (net (code "12") (name "ESP32_IO4") (class "Default")
      (node (ref "A1") (pin "26") (pinfunction "IO4_26") (pintype "bidirectional"))
      (node (ref "U14") (pin "9") (pinfunction "FRAME_9") (pintype "bidirectional"))
    )
    (net (code "13") (name "ESP32_IO5") (class "Default")
      (node (ref "A1") (pin "29") (pinfunction "IO5_29") (pintype "bidirectional"))
      (node (ref "U8") (pin "5") (pinfunction "*CS/A0_5") (pintype "passive"))
    )
    (net (code "14") (name "ESP32_IO12") (class "Default")
      (node (ref "A1") (pin "14") (pinfunction "IO12_14") (pintype "bidirectional"))
      (node (ref "CON2") (pin "11") (pinfunction "11_11") (pintype "passive"))
      (node (ref "CON3") (pin "P$21") (pinfunction "Y3_P$21") (pintype "output"))
    )
    (net (code "15") (name "ESP32_IO13") (class "Default")
      (node (ref "A1") (pin "16") (pinfunction "IO13_16") (pintype "bidirectional"))
      (node (ref "CON2") (pin "13") (pinfunction "13_13") (pintype "passive"))
      (node (ref "CON3") (pin "P$22") (pinfunction "Y4_P$22") (pintype "output"))
    )
    (net (code "16") (name "ESP32_IO14") (class "Default")
      (node (ref "A1") (pin "13") (pinfunction "IO14_13") (pintype "bidirectional"))
      (node (ref "CON2") (pin "12") (pinfunction "12_12") (pintype "passive"))
      (node (ref "CON3") (pin "P$19") (pinfunction "Y2_P$19") (pintype "output"))
    )
    (net (code "17") (name "ESP32_IO15") (class "Default")
      (node (ref "A1") (pin "23") (pinfunction "IO15_23") (pintype "bidirectional"))
      (node (ref "CON2") (pin "14") (pinfunction "14_14") (pintype "passive"))
      (node (ref "CON3") (pin "P$20") (pinfunction "Y5_P$20") (pintype "output"))
    )
    (net (code "18") (name "ESP32_IO18") (class "Default")
      (node (ref "A1") (pin "30") (pinfunction "IO18_30") (pintype "bidirectional"))
      (node (ref "U8") (pin "4") (pinfunction "SCLK/SCL_4") (pintype "passive"))
    )
    (net (code "19") (name "ESP32_IO19") (class "Default")
      (node (ref "A1") (pin "31") (pinfunction "IO19_31") (pintype "bidirectional"))
      (node (ref "U8") (pin "3") (pinfunction "MISO/SDA_3") (pintype "passive"))
    )
    (net (code "20") (name "ESP32_IO21") (class "Default")
      (node (ref "A1") (pin "33") (pinfunction "IO21_33") (pintype "bidirectional"))
      (node (ref "R13") (pin "2") (pinfunction "2_2") (pintype "passive"))
      (node (ref "U8") (pin "7") (pinfunction "*IRQ_7") (pintype "passive"))
    )
    (net (code "21") (name "ESP32_IO22") (class "Default")
      (node (ref "A1") (pin "36") (pinfunction "IO22_36") (pintype "bidirectional"))
      (node (ref "CON3") (pin "P$17") (pinfunction "PCLK_P$17") (pintype "output"))
    )
    (net (code "22") (name "ESP32_IO23") (class "Default")
      (node (ref "A1") (pin "37") (pinfunction "IO23_37") (pintype "bidirectional"))
      (node (ref "U8") (pin "6") (pinfunction "MOSI/A1_6") (pintype "passive"))
    )
    (net (code "23") (name "ESP32_IO25") (class "Default")
      (node (ref "A1") (pin "10") (pinfunction "IO25_10") (pintype "bidirectional"))
      (node (ref "CON3") (pin "P$7") (pinfunction "VSYNC_P$7") (pintype "output"))
    )
    (net (code "24") (name "ESP32_IO26") (class "Default")
      (node (ref "A1") (pin "11") (pinfunction "IO26_11") (pintype "bidirectional"))
      (node (ref "CON3") (pin "P$3") (pinfunction "SIO_D_P$3") (pintype "bidirectional"))
      (node (ref "R9") (pin "1") (pinfunction "1_1") (pintype "passive"))
    )
    (net (code "25") (name "ESP32_IO27") (class "Default")
      (node (ref "A1") (pin "12") (pinfunction "IO27_12") (pintype "bidirectional"))
      (node (ref "CON3") (pin "P$9") (pinfunction "HREF_P$9") (pintype "output"))
    )
    (net (code "26") (name "ESP32_IO32") (class "Default")
      (node (ref "A1") (pin "8") (pinfunction "IO32_8") (pintype "bidirectional"))
      (node (ref "U14") (pin "7") (pinfunction "ADCDAT_7") (pintype "output"))
    )
    (net (code "27") (name "ESP32_IO33") (class "Default")
      (node (ref "A1") (pin "9") (pinfunction "IO33_9") (pintype "bidirectional"))
      (node (ref "CON1") (pin "14") (pinfunction "14_14") (pintype "passive"))
      (node (ref "R8") (pin "1") (pinfunction "1_1") (pintype "passive"))
      (node (ref "U1") (pin "4") (pinfunction "SDA_4") (pintype "bidirectional"))
      (node (ref "U14") (pin "14") (pinfunction "SDIN_14") (pintype "bidirectional"))
      (node (ref "U2") (pin "3") (pinfunction "SDI_3") (pintype "bidirectional"))
      (node (ref "U3") (pin "9") (pinfunction "SDA_9") (pintype "bidirectional"))
    )
    (net (code "28") (name "ESP32_IO34") (class "Default")
      (node (ref "A1") (pin "6") (pinfunction "IO34_6") (pintype "input"))
      (node (ref "CON3") (pin "P$18") (pinfunction "Y6_P$18") (pintype "output"))
    )
    (net (code "29") (name "ESP32_IO35") (class "Default")
      (node (ref "A1") (pin "7") (pinfunction "IO35_7") (pintype "input"))
      (node (ref "CON3") (pin "P$16") (pinfunction "Y7_P$16") (pintype "output"))
    )
    (net (code "30") (name "ESP32_IO36") (class "Default")
      (node (ref "A1") (pin "4") (pinfunction "SENSOR_VP_4") (pintype "input"))
      (node (ref "CON3") (pin "P$12") (pinfunction "Y9_P$12") (pintype "output"))
    )
    (net (code "31") (name "ESP32_IO39") (class "Default")
      (node (ref "A1") (pin "5") (pinfunction "SENSOR_VN_5") (pintype "input"))
      (node (ref "CON3") (pin "P$14") (pinfunction "Y8_P$14") (pintype "output"))
    )
    (net (code "32") (name "GND") (class "Default")
      (node (ref "A1") (pin "1") (pinfunction "GND_1") (pintype "power_in"))
      (node (ref "A1") (pin "15") (pinfunction "GND_15") (pintype "power_in"))
      (node (ref "A1") (pin "38") (pinfunction "GND_38") (pintype "power_in"))
      (node (ref "A1") (pin "39") (pinfunction "EXP_39") (pintype "power_in"))
      (node (ref "C1") (pin "2") (pinfunction "2_2") (pintype "passive"))
      (node (ref "C10") (pin "2") (pinfunction "2_2") (pintype "passive"))
      (node (ref "C11") (pin "2") (pinfunction "2_2") (pintype "passive"))
      (node (ref "C12") (pin "2") (pinfunction "2_2") (pintype "passive"))
      (node (ref "C13") (pin "2") (pinfunction "2_2") (pintype "passive"))
      (node (ref "C14") (pin "2") (pinfunction "2_2") (pintype "passive"))
      (node (ref "C15") (pin "2") (pinfunction "2_2") (pintype "passive"))
      (node (ref "C17") (pin "2") (pinfunction "2_2") (pintype "passive"))
      (node (ref "C18") (pin "2") (pinfunction "2_2") (pintype "passive"))
      (node (ref "C19") (pin "2") (pinfunction "2_2") (pintype "passive"))
      (node (ref "C2") (pin "2") (pinfunction "2_2") (pintype "passive"))
      (node (ref "C20") (pin "2") (pinfunction "2_2") (pintype "passive"))
      (node (ref "C21") (pin "1") (pinfunction "1_1") (pintype "passive"))
      (node (ref "C22") (pin "1") (pinfunction "1_1") (pintype "passive"))
      (node (ref "C27") (pin "2") (pinfunction "2_2") (pintype "passive"))
      (node (ref "C28") (pin "2") (pinfunction "2_2") (pintype "passive"))
      (node (ref "C29") (pin "2") (pinfunction "2_2") (pintype "passive"))
      (node (ref "C3") (pin "2") (pinfunction "2_2") (pintype "passive"))
      (node (ref "C30") (pin "2") (pinfunction "2_2") (pintype "passive"))
      (node (ref "C31") (pin "2") (pinfunction "2_2") (pintype "passive"))
      (node (ref "C32") (pin "2") (pinfunction "2_2") (pintype "passive"))
      (node (ref "C33") (pin "2") (pinfunction "2_2") (pintype "passive"))
      (node (ref "C34") (pin "2") (pinfunction "2_2") (pintype "passive"))
      (node (ref "C35") (pin "2") (pinfunction "2_2") (pintype "passive"))
      (node (ref "C36") (pin "2") (pinfunction "2_2") (pintype "passive"))
      (node (ref "C38") (pin "2") (pinfunction "2_2") (pintype "passive"))
      (node (ref "C39") (pin "2") (pinfunction "2_2") (pintype "passive"))
      (node (ref "C4") (pin "2") (pinfunction "2_2") (pintype "passive"))
      (node (ref "C40") (pin "2") (pinfunction "2_2") (pintype "passive"))
      (node (ref "C42") (pin "2") (pinfunction "2_2") (pintype "passive"))
      (node (ref "C43") (pin "2") (pinfunction "2_2") (pintype "passive"))
      (node (ref "C44") (pin "2") (pinfunction "2_2") (pintype "passive"))
      (node (ref "C45") (pin "-") (pinfunction "-_-") (pintype "passive"))
      (node (ref "C46") (pin "-") (pinfunction "-_-") (pintype "passive"))
      (node (ref "C5") (pin "2") (pinfunction "2_2") (pintype "passive"))
      (node (ref "C6") (pin "2") (pinfunction "2_2") (pintype "passive"))
      (node (ref "C7") (pin "2") (pinfunction "2_2") (pintype "passive"))
      (node (ref "C8") (pin "2") (pinfunction "2_2") (pintype "passive"))
      (node (ref "C9") (pin "2") (pinfunction "2_2") (pintype "passive"))
      (node (ref "CON1") (pin "1") (pinfunction "1_1") (pintype "passive"))
      (node (ref "CON1") (pin "3") (pinfunction "3_3") (pintype "passive"))
      (node (ref "CON3") (pin "P$15") (pinfunction "DGND_P$15") (pintype "power_in"))
      (node (ref "CON3") (pin "P$2") (pinfunction "AGND_P$2") (pintype "power_in"))
      (node (ref "D1") (pin "3") (pinfunction "GND_3") (pintype "bidirectional"))
      (node (ref "D2") (pin "3") (pinfunction "GND_3") (pintype "bidirectional"))
      (node (ref "D3") (pin "3") (pinfunction "GND_3") (pintype "bidirectional"))
      (node (ref "D4") (pin "3") (pinfunction "GND_3") (pintype "bidirectional"))
      (node (ref "D5") (pin "A") (pinfunction "A_A") (pintype "passive"))
      (node (ref "R14") (pin "1") (pinfunction "1_1") (pintype "passive"))
      (node (ref "R20") (pin "2") (pinfunction "2_2") (pintype "passive"))
      (node (ref "R23") (pin "2") (pinfunction "2_2") (pintype "passive"))
      (node (ref "R26") (pin "2") (pinfunction "2_2") (pintype "passive"))
      (node (ref "R29") (pin "2") (pinfunction "2_2") (pintype "passive"))
      (node (ref "R3") (pin "1") (pinfunction "1_1") (pintype "passive"))
      (node (ref "R33") (pin "2") (pinfunction "2_2") (pintype "passive"))
      (node (ref "R34") (pin "2") (pinfunction "2_2") (pintype "passive"))
      (node (ref "R7") (pin "1") (pinfunction "1_1") (pintype "passive"))
      (node (ref "S1") (pin "1") (pinfunction "1_1") (pintype "passive"))
      (node (ref "S1") (pin "2") (pinfunction "2_2") (pintype "passive"))
      (node (ref "S2") (pin "1") (pinfunction "1_1") (pintype "passive"))
      (node (ref "S2") (pin "2") (pinfunction "2_2") (pintype "passive"))
      (node (ref "U$7") (pin "3") (pinfunction "VSS_3") (pintype "power_in"))
      (node (ref "U1") (pin "2") (pinfunction "ADDR_2") (pintype "input"))
      (node (ref "U1") (pin "3") (pinfunction "GND_3") (pintype "power_in"))
      (node (ref "U12") (pin "7") (pinfunction "GND_7") (pintype "power_in"))
      (node (ref "U12") (pin "9") (pinfunction "GND_9") (pintype "power_in"))
      (node (ref "U14") (pin "15") (pinfunction "MODE_15") (pintype "input"))
      (node (ref "U14") (pin "18") (pinfunction "SPKGND_18") (pintype "power_in"))
      (node (ref "U14") (pin "3") (pinfunction "AGND_3") (pintype "power_in"))
      (node (ref "U14") (pin "6") (pinfunction "DGND_6") (pintype "power_in"))
      (node (ref "U14") (pin "EP") (pinfunction "AGND_EP") (pintype "power_in"))
      (node (ref "U17") (pin "2") (pinfunction "GND_2") (pintype "power_in"))
      (node (ref "U18") (pin "2") (pinfunction "GND_2") (pintype "power_in"))
      (node (ref "U2") (pin "1") (pinfunction "GND_1") (pintype "power_in"))
      (node (ref "U2") (pin "5") (pinfunction "SDO_5") (pintype "bidirectional"))
      (node (ref "U2") (pin "7") (pinfunction "GND_7") (pintype "power_in"))
      (node (ref "U3") (pin "1") (pinfunction "ADDR_1") (pintype "input"))
      (node (ref "U3") (pin "11") (pinfunction "EP_11") (pintype "power_in"))
      (node (ref "U3") (pin "7") (pinfunction "~{WAKE}_7") (pintype "input"))
      (node (ref "U4") (pin "5") (pinfunction "GND_5") (pintype "passive"))
      (node (ref "U5") (pin "5") (pinfunction "GND_5") (pintype "passive"))
      (node (ref "U6") (pin "5") (pinfunction "GND_5") (pintype "passive"))
      (node (ref "U7") (pin "5") (pinfunction "GND_5") (pintype "passive"))
      (node (ref "U8") (pin "10") (pinfunction "DGND_10") (pintype "power_in"))
      (node (ref "U8") (pin "46") (pinfunction "AGND_46") (pintype "power_in"))
      (node (ref "U8") (pin "49") (pinfunction "EP_49") (pintype "passive"))
      (node (ref "Y1") (pin "2") (pinfunction "GND_2") (pintype "passive"))
    )
    (net (code "33") (name "MAX_IO0") (class "Default")
      (node (ref "S8") (pin "1B") (pinfunction "1B_1B") (pintype "passive"))
      (node (ref "U8") (pin "11") (pinfunction "GPIO0_11") (pintype "passive"))
    )
    (net (code "34") (name "MAX_IO1") (class "Default")
      (node (ref "S8") (pin "2B") (pinfunction "2B_2B") (pintype "passive"))
      (node (ref "U8") (pin "12") (pinfunction "GPIO1_12") (pintype "passive"))
    )
    (net (code "35") (name "MAX_IO2") (class "Default")
      (node (ref "S8") (pin "3B") (pinfunction "3B_3B") (pintype "passive"))
      (node (ref "U8") (pin "13") (pinfunction "GPIO2_13") (pintype "passive"))
    )
    (net (code "36") (name "MAX_IO3") (class "Default")
      (node (ref "S8") (pin "4B") (pinfunction "4B_4B") (pintype "passive"))
      (node (ref "U8") (pin "14") (pinfunction "GPIO3_14") (pintype "passive"))
    )
    (net (code "37") (name "MAX_IO4") (class "Default")
      (node (ref "S8") (pin "5B") (pinfunction "5B_5B") (pintype "passive"))
      (node (ref "U8") (pin "19") (pinfunction "GPIO4_19") (pintype "passive"))
    )
    (net (code "38") (name "MAX_IO5") (class "Default")
      (node (ref "S8") (pin "6B") (pinfunction "6B_6B") (pintype "passive"))
      (node (ref "U8") (pin "20") (pinfunction "GPIO5_20") (pintype "passive"))
    )
    (net (code "39") (name "MAX_IO6") (class "Default")
      (node (ref "S8") (pin "7B") (pinfunction "7B_7B") (pintype "passive"))
      (node (ref "U8") (pin "21") (pinfunction "GPIO6_21") (pintype "passive"))
    )
    (net (code "40") (name "MAX_IO7") (class "Default")
      (node (ref "S8") (pin "8B") (pinfunction "8B_8B") (pintype "passive"))
      (node (ref "U8") (pin "22") (pinfunction "GPIO7_22") (pintype "passive"))
    )
    (net (code "41") (name "MAX_IO8") (class "Default")
      (node (ref "CON1") (pin "6") (pinfunction "6_6") (pintype "passive"))
      (node (ref "U8") (pin "27") (pinfunction "GPIO8_27") (pintype "passive"))
    )
    (net (code "42") (name "MAX_IO9") (class "Default")
      (node (ref "CON1") (pin "8") (pinfunction "8_8") (pintype "passive"))
      (node (ref "U8") (pin "28") (pinfunction "GPIO9_28") (pintype "passive"))
    )
    (net (code "43") (name "MAX_IO10") (class "Default")
      (node (ref "CON1") (pin "10") (pinfunction "10_10") (pintype "passive"))
      (node (ref "U8") (pin "29") (pinfunction "GPIO10_29") (pintype "passive"))
    )
    (net (code "44") (name "MAX_IO11") (class "Default")
      (node (ref "CON1") (pin "12") (pinfunction "12_12") (pintype "passive"))
      (node (ref "U8") (pin "30") (pinfunction "GPIO11_30") (pintype "passive"))
    )
    (net (code "45") (name "MAX_IO12") (class "Default")
      (node (ref "CON1") (pin "11") (pinfunction "11_11") (pintype "passive"))
      (node (ref "U8") (pin "35") (pinfunction "GPIO12_35") (pintype "passive"))
    )
    (net (code "46") (name "MAX_IO13") (class "Default")
      (node (ref "CON1") (pin "9") (pinfunction "9_9") (pintype "passive"))
      (node (ref "U8") (pin "36") (pinfunction "GPIO13_36") (pintype "passive"))
    )
    (net (code "47") (name "MAX_IO14") (class "Default")
      (node (ref "CON1") (pin "7") (pinfunction "7_7") (pintype "passive"))
      (node (ref "U8") (pin "37") (pinfunction "GPIO14_37") (pintype "passive"))
    )
    (net (code "48") (name "MAX_IO15") (class "Default")
      (node (ref "CON1") (pin "5") (pinfunction "5_5") (pintype "passive"))
      (node (ref "U8") (pin "38") (pinfunction "GPIO15_38") (pintype "passive"))
    )
    (net (code "49") (name "Net-(C23-Pad2)") (class "Default")
      (node (ref "C23") (pin "2") (pinfunction "2_2") (pintype "passive"))
      (node (ref "R14") (pin "2") (pinfunction "2_2") (pintype "passive"))
      (node (ref "U$6") (pin "-") (pinfunction "-_-") (pintype "passive"))
    )
    (net (code "50") (name "Net-(C24-Pad2)") (class "Default")
      (node (ref "C24") (pin "2") (pinfunction "2_2") (pintype "passive"))
      (node (ref "C26") (pin "2") (pinfunction "2_2") (pintype "passive"))
      (node (ref "R15") (pin "2") (pinfunction "2_2") (pintype "passive"))
      (node (ref "R16") (pin "1") (pinfunction "1_1") (pintype "passive"))
      (node (ref "U$6") (pin "+") (pinfunction "+_+") (pintype "passive"))
    )
    (net (code "51") (name "Net-(C25-Pad2)") (class "Default")
      (node (ref "C25") (pin "2") (pinfunction "2_2") (pintype "passive"))
      (node (ref "C26") (pin "1") (pinfunction "1_1") (pintype "passive"))
      (node (ref "R15") (pin "1") (pinfunction "1_1") (pintype "passive"))
    )
    (net (code "52") (name "Net-(CON3-PWDN)") (class "Default")
      (node (ref "CON3") (pin "P$8") (pinfunction "PWDN_P$8") (pintype "input"))
      (node (ref "R3") (pin "2") (pinfunction "2_2") (pintype "passive"))
    )
    (net (code "53") (name "Net-(CON3-RESET)") (class "Default")
      (node (ref "C4") (pin "1") (pinfunction "1_1") (pintype "passive"))
      (node (ref "CON3") (pin "P$6") (pinfunction "RESET_P$6") (pintype "input"))
      (node (ref "R4") (pin "2") (pinfunction "2_2") (pintype "passive"))
    )
    (net (code "54") (name "Net-(L2-1)") (class "Default")
      (node (ref "C41") (pin "2") (pinfunction "2_2") (pintype "passive"))
      (node (ref "D5") (pin "C") (pinfunction "C_C") (pintype "passive"))
      (node (ref "L2") (pin "P$1") (pinfunction "1_P$1") (pintype "passive"))
      (node (ref "U12") (pin "8") (pinfunction "SW_8") (pintype "output"))
    )
    (net (code "55") (name "Net-(R2-Pad2)") (class "Default")
      (node (ref "R2") (pin "2") (pinfunction "2_2") (pintype "passive"))
      (node (ref "S2") (pin "3") (pinfunction "3_3") (pintype "passive"))
      (node (ref "S2") (pin "4") (pinfunction "4_4") (pintype "passive"))
    )
    (net (code "56") (name "Net-(R5-Pad2)") (class "Default")
      (node (ref "R5") (pin "2") (pinfunction "2_2") (pintype "passive"))
      (node (ref "R6") (pin "1") (pinfunction "1_1") (pintype "passive"))
    )
    (net (code "57") (name "Net-(SPR1-1)") (class "Default")
      (node (ref "SPR1") (pin "+") (pinfunction "1_+") (pintype "passive"))
      (node (ref "U14") (pin "17") (pinfunction "SPKOUTP_17") (pintype "output"))
    )
    (net (code "58") (name "Net-(SPR1-2)") (class "Default")
      (node (ref "SPR1") (pin "-") (pinfunction "2_-") (pintype "passive"))
      (node (ref "U14") (pin "19") (pinfunction "SPKOUTN_19") (pintype "output"))
    )
    (net (code "59") (name "Net-(U1-DVI)") (class "Default")
      (node (ref "C28") (pin "1") (pinfunction "1_1") (pintype "passive"))
      (node (ref "R17") (pin "1") (pinfunction "1_1") (pintype "passive"))
      (node (ref "U1") (pin "5") (pinfunction "DVI_5") (pintype "input"))
    )
    (net (code "60") (name "Net-(U3-PWM)") (class "Default")
      (node (ref "U3") (pin "4") (pinfunction "PWM_4") (pintype "output"))
      (node (ref "U3") (pin "5") (pinfunction "SENSE_5") (pintype "input"))
    )
    (net (code "61") (name "Net-(U3-~{RESET})") (class "Default")
      (node (ref "R30") (pin "1") (pinfunction "1_1") (pintype "passive"))
      (node (ref "U3") (pin "2") (pinfunction "~{RESET}_2") (pintype "input"))
    )
    (net (code "62") (name "Net-(U4-D)") (class "Default")
      (node (ref "U4") (pin "4") (pinfunction "D_4") (pintype "input"))
      (node (ref "U8") (pin "42") (pinfunction "TX3_42") (pintype "passive"))
    )
    (net (code "63") (name "Net-(U4-DE)") (class "Default")
      (node (ref "U4") (pin "2") (pinfunction "~{RE}_2") (pintype "input"))
      (node (ref "U4") (pin "3") (pinfunction "DE_3") (pintype "input"))
      (node (ref "U8") (pin "39") (pinfunction "*RTS3_39") (pintype "passive"))
    )
    (net (code "64") (name "Net-(U4-R)") (class "Default")
      (node (ref "U4") (pin "1") (pinfunction "R_1") (pintype "output"))
      (node (ref "U8") (pin "41") (pinfunction "RX3_41") (pintype "passive"))
    )
    (net (code "65") (name "Net-(U5-D)") (class "Default")
      (node (ref "U5") (pin "4") (pinfunction "D_4") (pintype "input"))
      (node (ref "U8") (pin "34") (pinfunction "TX2_34") (pintype "passive"))
    )
    (net (code "66") (name "Net-(U5-DE)") (class "Default")
      (node (ref "U5") (pin "2") (pinfunction "~{RE}_2") (pintype "input"))
      (node (ref "U5") (pin "3") (pinfunction "DE_3") (pintype "input"))
      (node (ref "U8") (pin "31") (pinfunction "*RTS2_31") (pintype "passive"))
    )
    (net (code "67") (name "Net-(U5-R)") (class "Default")
      (node (ref "U5") (pin "1") (pinfunction "R_1") (pintype "output"))
      (node (ref "U8") (pin "33") (pinfunction "RX2_33") (pintype "passive"))
    )
    (net (code "68") (name "Net-(U6-D)") (class "Default")
      (node (ref "U6") (pin "4") (pinfunction "D_4") (pintype "input"))
      (node (ref "U8") (pin "26") (pinfunction "TX1_26") (pintype "passive"))
    )
    (net (code "69") (name "Net-(U6-DE)") (class "Default")
      (node (ref "U6") (pin "2") (pinfunction "~{RE}_2") (pintype "input"))
      (node (ref "U6") (pin "3") (pinfunction "DE_3") (pintype "input"))
      (node (ref "U8") (pin "23") (pinfunction "*RTS1_23") (pintype "passive"))
    )
    (net (code "70") (name "Net-(U6-R)") (class "Default")
      (node (ref "U6") (pin "1") (pinfunction "R_1") (pintype "output"))
      (node (ref "U8") (pin "25") (pinfunction "RX1_25") (pintype "passive"))
    )
    (net (code "71") (name "Net-(U7-D)") (class "Default")
      (node (ref "U7") (pin "4") (pinfunction "D_4") (pintype "input"))
      (node (ref "U8") (pin "18") (pinfunction "TX0_18") (pintype "passive"))
    )
    (net (code "72") (name "Net-(U7-DE)") (class "Default")
      (node (ref "U7") (pin "2") (pinfunction "~{RE}_2") (pintype "input"))
      (node (ref "U7") (pin "3") (pinfunction "DE_3") (pintype "input"))
      (node (ref "U8") (pin "15") (pinfunction "*RTS0_15") (pintype "passive"))
    )
    (net (code "73") (name "Net-(U7-R)") (class "Default")
      (node (ref "U7") (pin "1") (pinfunction "R_1") (pintype "output"))
      (node (ref "U8") (pin "17") (pinfunction "RX0_17") (pintype "passive"))
    )
    (net (code "74") (name "Net-(U8-*RST)") (class "Default")
      (node (ref "C13") (pin "1") (pinfunction "1_1") (pintype "passive"))
      (node (ref "R12") (pin "2") (pinfunction "2_2") (pintype "passive"))
      (node (ref "U8") (pin "8") (pinfunction "*RST_8") (pintype "passive"))
    )
    (net (code "75") (name "Net-(U8-V18)") (class "Default")
      (node (ref "C14") (pin "1") (pinfunction "1_1") (pintype "passive"))
      (node (ref "U8") (pin "48") (pinfunction "V18_48") (pintype "power_in"))
    )
    (net (code "76") (name "Net-(U12-BOOT)") (class "Default")
      (node (ref "C41") (pin "1") (pinfunction "1_1") (pintype "passive"))
      (node (ref "U12") (pin "1") (pinfunction "BOOT_1") (pintype "power_in"))
    )
    (net (code "77") (name "Net-(U12-FB)") (class "Default")
      (node (ref "C37") (pin "2") (pinfunction "2_2") (pintype "passive"))
      (node (ref "R34") (pin "1") (pinfunction "1_1") (pintype "passive"))
      (node (ref "R35") (pin "2") (pinfunction "2_2") (pintype "passive"))
      (node (ref "R36") (pin "2") (pinfunction "2_2") (pintype "passive"))
      (node (ref "U12") (pin "5") (pinfunction "FB_5") (pintype "input"))
    )
    (net (code "78") (name "Net-(U12-RT{slash}SYNC)") (class "Default")
      (node (ref "R33") (pin "1") (pinfunction "1_1") (pintype "passive"))
      (node (ref "U12") (pin "4") (pinfunction "RT/SYNC_4") (pintype "input"))
    )
    (net (code "79") (name "Net-(U14-MICBIAS)") (class "Default")
      (node (ref "C25") (pin "1") (pinfunction "1_1") (pintype "passive"))
      (node (ref "R16") (pin "2") (pinfunction "2_2") (pintype "passive"))
      (node (ref "U14") (pin "1") (pinfunction "MICBIAS_1") (pintype "output"))
    )
    (net (code "80") (name "Net-(U14-MICN)") (class "Default")
      (node (ref "C23") (pin "1") (pinfunction "1_1") (pintype "passive"))
      (node (ref "U14") (pin "23") (pinfunction "MICN_23") (pintype "input"))
    )
    (net (code "81") (name "Net-(U14-MICP)") (class "Default")
      (node (ref "C24") (pin "1") (pinfunction "1_1") (pintype "passive"))
      (node (ref "U14") (pin "24") (pinfunction "MICP_24") (pintype "input"))
    )
    (net (code "82") (name "Net-(U14-SPKVDD)") (class "Default")
      (node (ref "C21") (pin "2") (pinfunction "2_2") (pintype "passive"))
      (node (ref "R31") (pin "2") (pinfunction "2_2") (pintype "passive"))
      (node (ref "U14") (pin "20") (pinfunction "SPKVDD_20") (pintype "power_in"))
    )
    (net (code "83") (name "Net-(U14-VMID)") (class "Default")
      (node (ref "C22") (pin "2") (pinfunction "2_2") (pintype "passive"))
      (node (ref "U14") (pin "22") (pinfunction "VMID_22") (pintype "bidirectional"))
    )
    (net (code "84") (name "Net-(U18-FB)") (class "Default")
      (node (ref "R5") (pin "1") (pinfunction "1_1") (pintype "passive"))
      (node (ref "R7") (pin "2") (pinfunction "2_2") (pintype "passive"))
      (node (ref "U18") (pin "4") (pinfunction "FB_4") (pintype "power_in"))
    )
    (net (code "85") (name "RS485_A0") (class "Default")
      (node (ref "CON2") (pin "1") (pinfunction "1_1") (pintype "passive"))
      (node (ref "D1") (pin "2") (pinfunction "IO2_2") (pintype "bidirectional"))
      (node (ref "R18") (pin "2") (pinfunction "2_2") (pintype "passive"))
      (node (ref "R19") (pin "1") (pinfunction "1_1") (pintype "passive"))
      (node (ref "U7") (pin "6") (pinfunction "A_6") (pintype "output"))
    )
    (net (code "86") (name "RS485_A1") (class "Default")
      (node (ref "CON2") (pin "3") (pinfunction "3_3") (pintype "passive"))
      (node (ref "D2") (pin "2") (pinfunction "IO2_2") (pintype "bidirectional"))
      (node (ref "R21") (pin "2") (pinfunction "2_2") (pintype "passive"))
      (node (ref "R22") (pin "1") (pinfunction "1_1") (pintype "passive"))
      (node (ref "U6") (pin "6") (pinfunction "A_6") (pintype "output"))
    )
    (net (code "87") (name "RS485_A2") (class "Default")
      (node (ref "CON2") (pin "5") (pinfunction "5_5") (pintype "passive"))
      (node (ref "D3") (pin "2") (pinfunction "IO2_2") (pintype "bidirectional"))
      (node (ref "R24") (pin "2") (pinfunction "2_2") (pintype "passive"))
      (node (ref "R25") (pin "1") (pinfunction "1_1") (pintype "passive"))
      (node (ref "U5") (pin "6") (pinfunction "A_6") (pintype "output"))
    )
    (net (code "88") (name "RS485_A3") (class "Default")
      (node (ref "CON2") (pin "7") (pinfunction "7_7") (pintype "passive"))
      (node (ref "D4") (pin "2") (pinfunction "IO2_2") (pintype "bidirectional"))
      (node (ref "R27") (pin "2") (pinfunction "2_2") (pintype "passive"))
      (node (ref "R28") (pin "1") (pinfunction "1_1") (pintype "passive"))
      (node (ref "U4") (pin "6") (pinfunction "A_6") (pintype "output"))
    )
    (net (code "89") (name "RS485_B0") (class "Default")
      (node (ref "CON2") (pin "2") (pinfunction "2_2") (pintype "passive"))
      (node (ref "D1") (pin "1") (pinfunction "IO1_1") (pintype "bidirectional"))
      (node (ref "R19") (pin "2") (pinfunction "2_2") (pintype "passive"))
      (node (ref "R20") (pin "1") (pinfunction "1_1") (pintype "passive"))
      (node (ref "U7") (pin "7") (pinfunction "B_7") (pintype "output"))
    )
    (net (code "90") (name "RS485_B1") (class "Default")
      (node (ref "CON2") (pin "4") (pinfunction "4_4") (pintype "passive"))
      (node (ref "D2") (pin "1") (pinfunction "IO1_1") (pintype "bidirectional"))
      (node (ref "R22") (pin "2") (pinfunction "2_2") (pintype "passive"))
      (node (ref "R23") (pin "1") (pinfunction "1_1") (pintype "passive"))
      (node (ref "U6") (pin "7") (pinfunction "B_7") (pintype "output"))
    )
    (net (code "91") (name "RS485_B2") (class "Default")
      (node (ref "CON2") (pin "6") (pinfunction "6_6") (pintype "passive"))
      (node (ref "D3") (pin "1") (pinfunction "IO1_1") (pintype "bidirectional"))
      (node (ref "R25") (pin "2") (pinfunction "2_2") (pintype "passive"))
      (node (ref "R26") (pin "1") (pinfunction "1_1") (pintype "passive"))
      (node (ref "U5") (pin "7") (pinfunction "B_7") (pintype "output"))
    )
    (net (code "92") (name "RS485_B3") (class "Default")
      (node (ref "CON2") (pin "8") (pinfunction "8_8") (pintype "passive"))
      (node (ref "D4") (pin "1") (pinfunction "IO1_1") (pintype "bidirectional"))
      (node (ref "R28") (pin "2") (pinfunction "2_2") (pintype "passive"))
      (node (ref "R29") (pin "1") (pinfunction "1_1") (pintype "passive"))
      (node (ref "U4") (pin "7") (pinfunction "B_7") (pintype "output"))
    )
    (net (code "93") (name "unconnected-(A1-SCK{slash}CLK-Pad20)") (class "Default")
      (node (ref "A1") (pin "20") (pinfunction "SCK/CLK_20") (pintype "bidirectional"))
    )
    (net (code "94") (name "unconnected-(A1-SCS{slash}CMD-Pad19)") (class "Default")
      (node (ref "A1") (pin "19") (pinfunction "SCS/CMD_19") (pintype "bidirectional"))
    )
    (net (code "95") (name "unconnected-(A1-SDI{slash}SD1-Pad22)") (class "Default")
      (node (ref "A1") (pin "22") (pinfunction "SDI/SD1_22") (pintype "bidirectional"))
    )
    (net (code "96") (name "unconnected-(A1-SDO{slash}SD0-Pad21)") (class "Default")
      (node (ref "A1") (pin "21") (pinfunction "SDO/SD0_21") (pintype "bidirectional"))
    )
    (net (code "97") (name "unconnected-(A1-SHD{slash}SD2-Pad17)") (class "Default")
      (node (ref "A1") (pin "17") (pinfunction "SHD/SD2_17") (pintype "bidirectional"))
    )
    (net (code "98") (name "unconnected-(A1-SWP{slash}SD3-Pad18)") (class "Default")
      (node (ref "A1") (pin "18") (pinfunction "SWP/SD3_18") (pintype "bidirectional"))
    )
    (net (code "99") (name "unconnected-(CON3-STROBE-PadP$1)") (class "Default")
      (node (ref "CON3") (pin "P$1") (pinfunction "STROBE_P$1") (pintype "output"))
    )
    (net (code "100") (name "unconnected-(CON3-Y0-PadP$24)") (class "Default")
      (node (ref "CON3") (pin "P$24") (pinfunction "Y0_P$24") (pintype "output"))
    )
    (net (code "101") (name "unconnected-(CON3-Y1-PadP$23)") (class "Default")
      (node (ref "CON3") (pin "P$23") (pinfunction "Y1_P$23") (pintype "output"))
    )
    (net (code "102") (name "unconnected-(U3-~{INT}-Pad3)") (class "Default")
      (node (ref "U3") (pin "3") (pinfunction "~{INT}_3") (pintype "output"))
    )
    (net (code "103") (name "unconnected-(U8-*CTS1-Pad24)") (class "Default")
      (node (ref "U8") (pin "24") (pinfunction "*CTS1_24") (pintype "passive"))
    )
    (net (code "104") (name "unconnected-(U8-*CTS2-Pad32)") (class "Default")
      (node (ref "U8") (pin "32") (pinfunction "*CTS2_32") (pintype "passive"))
    )
    (net (code "105") (name "unconnected-(U8-*CTS3-Pad40)") (class "Default")
      (node (ref "U8") (pin "40") (pinfunction "*CTS3_40") (pintype "passive"))
    )
    (net (code "106") (name "unconnected-(U8-XOUT-Pad44)") (class "Default")
      (node (ref "U8") (pin "44") (pinfunction "XOUT_44") (pintype "passive"))
    )
    (net (code "107") (name "unconnected-(U12-PGOOD-Pad6)") (class "Default")
      (node (ref "U12") (pin "6") (pinfunction "PGOOD_6") (pintype "output"))
    )
    (net (code "108") (name "unconnected-(U14-AUX-Pad21)") (class "Default")
      (node (ref "U14") (pin "21") (pinfunction "AUX_21") (pintype "input"))
    )
    (net (code "109") (name "unconnected-(U14-CSB{slash}GPIO-Pad12)") (class "Default")
      (node (ref "U14") (pin "12") (pinfunction "CSB/GPIO_12") (pintype "bidirectional"))
    )
    (net (code "110") (name "unconnected-(U14-MONOOUT-Pad16)") (class "Default")
      (node (ref "U14") (pin "16") (pinfunction "MONOOUT_16") (pintype "output"))
    )
    (net (code "111") (name "unconnected-(Y1-~{ST}-Pad1)") (class "Default")
      (node (ref "Y1") (pin "1") (pinfunction "~{ST}_1") (pintype "input"))
    )
  )
)
